# ProPrj___2024-10-15.net
KiCad netlist of a schematic drawn in EasyEDA Pro
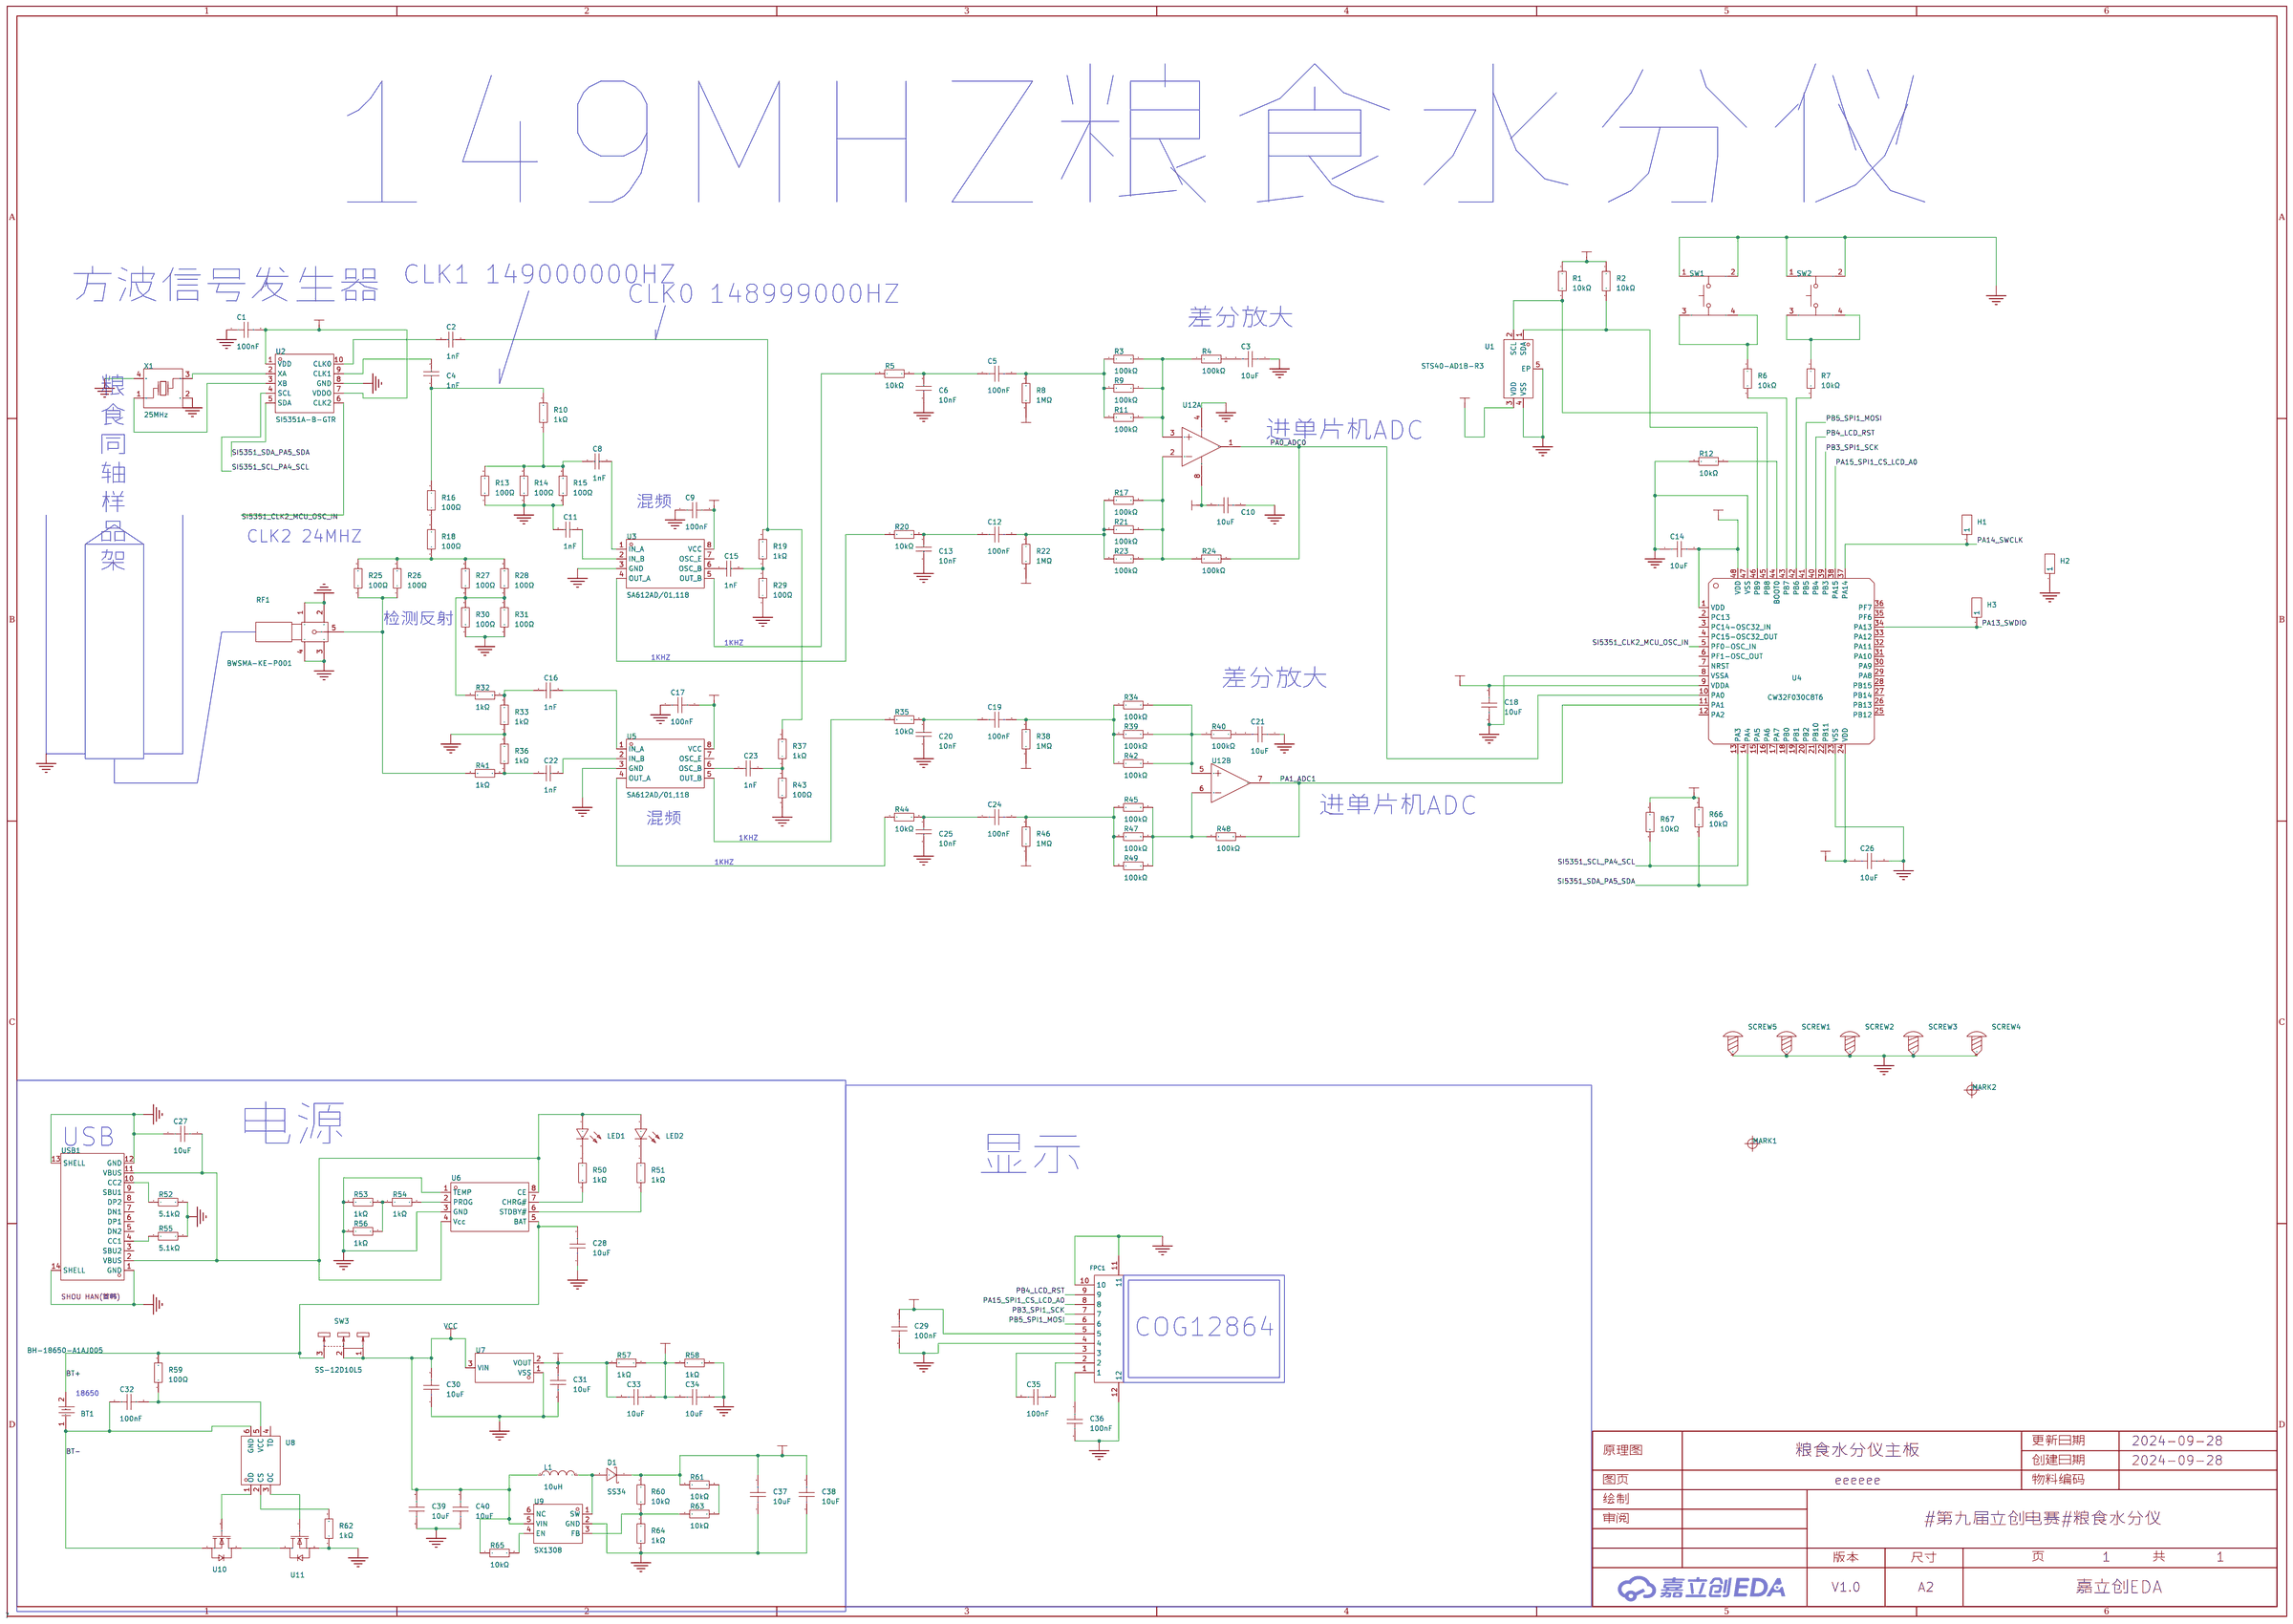
[diagram p0: schematic sheet]

(export (version "E")
  (design (tool "Eeschema 10.0.6"))
  (components
    (comp (ref "BT1")
      (value "BH-18650-A1AJ005")
      (footprint "easyedapro:BAT-TH_BH-18650-A1AJ005")
      (description "连接器类型:电池盒;适用电池规格:CR18650;触点电镀:镍;工作温度范围:-10°C~+100°C;")
      (fields (field (name "Manufacturer") "MYOUNG(美阳)"))
      (libsource (lib "easyedapro") (part "BH-18650-A1AJ005"))
    )
    (comp (ref "C1")
      (value "100nF")
      (footprint "easyedapro:C0603")
      (description "容值:100nF;精度:±10%;额定电压:50V;材质(温度系数):X7R;")
      (fields
        (field (name "Manufacturer Part") "CC0603KRX7R9BB104")
        (field (name "Manufacturer") "YAGEO(国巨)")
      )
      (libsource (lib "easyedapro") (part "CC0603KRX7R9BB104"))
    )
    (comp (ref "C2")
      (value "1nF")
      (footprint "easyedapro:C0603")
      (description "容值:1nF;精度:±5%;额定电压:50V;材质(温度系数):NP0;")
      (fields
        (field (name "Manufacturer Part") "CC0603JRNPO9BN102")
        (field (name "Manufacturer") "YAGEO(国巨)")
      )
      (libsource (lib "easyedapro") (part "CC0603JRNPO9BN102"))
    )
    (comp (ref "C3")
      (value "10uF")
      (footprint "easyedapro:C0603")
      (description "容值:10uF;精度:±10%;额定电压:10V;材质(温度系数):X5R;")
      (fields
        (field (name "Manufacturer Part") "CL10A106KP8NNNC")
        (field (name "Manufacturer") "SAMSUNG(三星)")
      )
      (libsource (lib "easyedapro") (part "CL10A106KP8NNNC"))
    )
    (comp (ref "C4")
      (value "1nF")
      (footprint "easyedapro:C0603")
      (description "容值:1nF;精度:±5%;额定电压:50V;材质(温度系数):NP0;")
      (fields
        (field (name "Manufacturer Part") "CC0603JRNPO9BN102")
        (field (name "Manufacturer") "YAGEO(国巨)")
      )
      (libsource (lib "easyedapro") (part "CC0603JRNPO9BN102"))
    )
    (comp (ref "C5")
      (value "100nF")
      (footprint "easyedapro:C0603")
      (description "容值:100nF;精度:±10%;额定电压:50V;材质(温度系数):X7R;")
      (fields
        (field (name "Manufacturer Part") "CC0603KRX7R9BB104")
        (field (name "Manufacturer") "YAGEO(国巨)")
      )
      (libsource (lib "easyedapro") (part "CC0603KRX7R9BB104"))
    )
    (comp (ref "C6")
      (value "10nF")
      (footprint "easyedapro:C0603")
      (description "容值:10nF;精度:±10%;额定电压:50V;材质(温度系数):X7R;")
      (fields
        (field (name "Manufacturer Part") "CC0603KRX7R9BB103")
        (field (name "Manufacturer") "YAGEO(国巨)")
      )
      (libsource (lib "easyedapro") (part "CC0603KRX7R9BB103"))
    )
    (comp (ref "C8")
      (value "1nF")
      (footprint "easyedapro:C0603")
      (description "容值:1nF;精度:±5%;额定电压:50V;材质(温度系数):NP0;")
      (fields
        (field (name "Manufacturer Part") "CC0603JRNPO9BN102")
        (field (name "Manufacturer") "YAGEO(国巨)")
      )
      (libsource (lib "easyedapro") (part "CC0603JRNPO9BN102"))
    )
    (comp (ref "C9")
      (value "100nF")
      (footprint "easyedapro:C0603")
      (description "容值:100nF;精度:±10%;额定电压:50V;材质(温度系数):X7R;")
      (fields
        (field (name "Manufacturer Part") "CC0603KRX7R9BB104")
        (field (name "Manufacturer") "YAGEO(国巨)")
      )
      (libsource (lib "easyedapro") (part "CC0603KRX7R9BB104"))
    )
    (comp (ref "C10")
      (value "10uF")
      (footprint "easyedapro:C0603")
      (description "容值:10uF;精度:±10%;额定电压:10V;材质(温度系数):X5R;")
      (fields
        (field (name "Manufacturer Part") "CL10A106KP8NNNC")
        (field (name "Manufacturer") "SAMSUNG(三星)")
      )
      (libsource (lib "easyedapro") (part "CL10A106KP8NNNC"))
    )
    (comp (ref "C11")
      (value "1nF")
      (footprint "easyedapro:C0603")
      (description "容值:1nF;精度:±5%;额定电压:50V;材质(温度系数):NP0;")
      (fields
        (field (name "Manufacturer Part") "CC0603JRNPO9BN102")
        (field (name "Manufacturer") "YAGEO(国巨)")
      )
      (libsource (lib "easyedapro") (part "CC0603JRNPO9BN102"))
    )
    (comp (ref "C12")
      (value "100nF")
      (footprint "easyedapro:C0603")
      (description "容值:100nF;精度:±10%;额定电压:50V;材质(温度系数):X7R;")
      (fields
        (field (name "Manufacturer Part") "CC0603KRX7R9BB104")
        (field (name "Manufacturer") "YAGEO(国巨)")
      )
      (libsource (lib "easyedapro") (part "CC0603KRX7R9BB104"))
    )
    (comp (ref "C13")
      (value "10nF")
      (footprint "easyedapro:C0603")
      (description "容值:10nF;精度:±10%;额定电压:50V;材质(温度系数):X7R;")
      (fields
        (field (name "Manufacturer Part") "CC0603KRX7R9BB103")
        (field (name "Manufacturer") "YAGEO(国巨)")
      )
      (libsource (lib "easyedapro") (part "CC0603KRX7R9BB103"))
    )
    (comp (ref "C14")
      (value "10uF")
      (footprint "easyedapro:C0603")
      (description "容值:10uF;精度:±10%;额定电压:10V;材质(温度系数):X5R;")
      (fields
        (field (name "Manufacturer Part") "CL10A106KP8NNNC")
        (field (name "Manufacturer") "SAMSUNG(三星)")
      )
      (libsource (lib "easyedapro") (part "CL10A106KP8NNNC"))
    )
    (comp (ref "C15")
      (value "1nF")
      (footprint "easyedapro:C0603")
      (description "容值:1nF;精度:±5%;额定电压:50V;材质(温度系数):NP0;")
      (fields
        (field (name "Manufacturer Part") "CC0603JRNPO9BN102")
        (field (name "Manufacturer") "YAGEO(国巨)")
      )
      (libsource (lib "easyedapro") (part "CC0603JRNPO9BN102"))
    )
    (comp (ref "C16")
      (value "1nF")
      (footprint "easyedapro:C0603")
      (description "容值:1nF;精度:±5%;额定电压:50V;材质(温度系数):NP0;")
      (fields
        (field (name "Manufacturer Part") "CC0603JRNPO9BN102")
        (field (name "Manufacturer") "YAGEO(国巨)")
      )
      (libsource (lib "easyedapro") (part "CC0603JRNPO9BN102"))
    )
    (comp (ref "C17")
      (value "100nF")
      (footprint "easyedapro:C0603")
      (description "容值:100nF;精度:±10%;额定电压:50V;材质(温度系数):X7R;")
      (fields
        (field (name "Manufacturer Part") "CC0603KRX7R9BB104")
        (field (name "Manufacturer") "YAGEO(国巨)")
      )
      (libsource (lib "easyedapro") (part "CC0603KRX7R9BB104"))
    )
    (comp (ref "C18")
      (value "10uF")
      (footprint "easyedapro:C0603")
      (description "容值:10uF;精度:±10%;额定电压:10V;材质(温度系数):X5R;")
      (fields
        (field (name "Manufacturer Part") "CL10A106KP8NNNC")
        (field (name "Manufacturer") "SAMSUNG(三星)")
      )
      (libsource (lib "easyedapro") (part "CL10A106KP8NNNC"))
    )
    (comp (ref "C19")
      (value "100nF")
      (footprint "easyedapro:C0603")
      (description "容值:100nF;精度:±10%;额定电压:50V;材质(温度系数):X7R;")
      (fields
        (field (name "Manufacturer Part") "CC0603KRX7R9BB104")
        (field (name "Manufacturer") "YAGEO(国巨)")
      )
      (libsource (lib "easyedapro") (part "CC0603KRX7R9BB104"))
    )
    (comp (ref "C20")
      (value "10nF")
      (footprint "easyedapro:C0603")
      (description "容值:10nF;精度:±10%;额定电压:50V;材质(温度系数):X7R;")
      (fields
        (field (name "Manufacturer Part") "CC0603KRX7R9BB103")
        (field (name "Manufacturer") "YAGEO(国巨)")
      )
      (libsource (lib "easyedapro") (part "CC0603KRX7R9BB103"))
    )
    (comp (ref "C21")
      (value "10uF")
      (footprint "easyedapro:C0603")
      (description "容值:10uF;精度:±10%;额定电压:10V;材质(温度系数):X5R;")
      (fields
        (field (name "Manufacturer Part") "CL10A106KP8NNNC")
        (field (name "Manufacturer") "SAMSUNG(三星)")
      )
      (libsource (lib "easyedapro") (part "CL10A106KP8NNNC"))
    )
    (comp (ref "C22")
      (value "1nF")
      (footprint "easyedapro:C0603")
      (description "容值:1nF;精度:±5%;额定电压:50V;材质(温度系数):NP0;")
      (fields
        (field (name "Manufacturer Part") "CC0603JRNPO9BN102")
        (field (name "Manufacturer") "YAGEO(国巨)")
      )
      (libsource (lib "easyedapro") (part "CC0603JRNPO9BN102"))
    )
    (comp (ref "C23")
      (value "1nF")
      (footprint "easyedapro:C0603")
      (description "容值:1nF;精度:±5%;额定电压:50V;材质(温度系数):NP0;")
      (fields
        (field (name "Manufacturer Part") "CC0603JRNPO9BN102")
        (field (name "Manufacturer") "YAGEO(国巨)")
      )
      (libsource (lib "easyedapro") (part "CC0603JRNPO9BN102"))
    )
    (comp (ref "C24")
      (value "100nF")
      (footprint "easyedapro:C0603")
      (description "容值:100nF;精度:±10%;额定电压:50V;材质(温度系数):X7R;")
      (fields
        (field (name "Manufacturer Part") "CC0603KRX7R9BB104")
        (field (name "Manufacturer") "YAGEO(国巨)")
      )
      (libsource (lib "easyedapro") (part "CC0603KRX7R9BB104"))
    )
    (comp (ref "C25")
      (value "10nF")
      (footprint "easyedapro:C0603")
      (description "容值:10nF;精度:±10%;额定电压:50V;材质(温度系数):X7R;")
      (fields
        (field (name "Manufacturer Part") "CC0603KRX7R9BB103")
        (field (name "Manufacturer") "YAGEO(国巨)")
      )
      (libsource (lib "easyedapro") (part "CC0603KRX7R9BB103"))
    )
    (comp (ref "C26")
      (value "10uF")
      (footprint "easyedapro:C0603")
      (description "容值:10uF;精度:±10%;额定电压:10V;材质(温度系数):X5R;")
      (fields
        (field (name "Manufacturer Part") "CL10A106KP8NNNC")
        (field (name "Manufacturer") "SAMSUNG(三星)")
      )
      (libsource (lib "easyedapro") (part "CL10A106KP8NNNC"))
    )
    (comp (ref "C27")
      (value "10uF")
      (footprint "easyedapro:C0603")
      (description "容值:10uF;精度:±10%;额定电压:10V;材质(温度系数):X5R;")
      (fields
        (field (name "Manufacturer Part") "CL10A106KP8NNNC")
        (field (name "Manufacturer") "SAMSUNG(三星)")
      )
      (libsource (lib "easyedapro") (part "CL10A106KP8NNNC"))
    )
    (comp (ref "C28")
      (value "10uF")
      (footprint "easyedapro:C0603")
      (description "容值:10uF;精度:±10%;额定电压:10V;材质(温度系数):X5R;")
      (fields
        (field (name "Manufacturer Part") "CL10A106KP8NNNC")
        (field (name "Manufacturer") "SAMSUNG(三星)")
      )
      (libsource (lib "easyedapro") (part "CL10A106KP8NNNC"))
    )
    (comp (ref "C29")
      (value "100nF")
      (footprint "easyedapro:C0603")
      (description "容值:100nF;精度:±10%;额定电压:50V;材质(温度系数):X7R;")
      (fields
        (field (name "Manufacturer Part") "CC0603KRX7R9BB104")
        (field (name "Manufacturer") "YAGEO(国巨)")
      )
      (libsource (lib "easyedapro") (part "CC0603KRX7R9BB104"))
    )
    (comp (ref "C30")
      (value "10uF")
      (footprint "easyedapro:C0603")
      (description "容值:10uF;精度:±10%;额定电压:10V;材质(温度系数):X5R;")
      (fields
        (field (name "Manufacturer Part") "CL10A106KP8NNNC")
        (field (name "Manufacturer") "SAMSUNG(三星)")
      )
      (libsource (lib "easyedapro") (part "CL10A106KP8NNNC"))
    )
    (comp (ref "C31")
      (value "10uF")
      (footprint "easyedapro:C0603")
      (description "容值:10uF;精度:±10%;额定电压:10V;材质(温度系数):X5R;")
      (fields
        (field (name "Manufacturer Part") "CL10A106KP8NNNC")
        (field (name "Manufacturer") "SAMSUNG(三星)")
      )
      (libsource (lib "easyedapro") (part "CL10A106KP8NNNC"))
    )
    (comp (ref "C32")
      (value "100nF")
      (footprint "easyedapro:C0603")
      (description "容值:100nF;精度:±10%;额定电压:50V;材质(温度系数):X7R;")
      (fields
        (field (name "Manufacturer Part") "CC0603KRX7R9BB104")
        (field (name "Manufacturer") "YAGEO(国巨)")
      )
      (libsource (lib "easyedapro") (part "CC0603KRX7R9BB104"))
    )
    (comp (ref "C33")
      (value "10uF")
      (footprint "easyedapro:C0603")
      (description "容值:10uF;精度:±10%;额定电压:10V;材质(温度系数):X5R;")
      (fields
        (field (name "Manufacturer Part") "CL10A106KP8NNNC")
        (field (name "Manufacturer") "SAMSUNG(三星)")
      )
      (libsource (lib "easyedapro") (part "CL10A106KP8NNNC"))
    )
    (comp (ref "C34")
      (value "10uF")
      (footprint "easyedapro:C0603")
      (description "容值:10uF;精度:±10%;额定电压:10V;材质(温度系数):X5R;")
      (fields
        (field (name "Manufacturer Part") "CL10A106KP8NNNC")
        (field (name "Manufacturer") "SAMSUNG(三星)")
      )
      (libsource (lib "easyedapro") (part "CL10A106KP8NNNC"))
    )
    (comp (ref "C35")
      (value "100nF")
      (footprint "easyedapro:C0603")
      (description "容值:100nF;精度:±10%;额定电压:50V;材质(温度系数):X7R;")
      (fields
        (field (name "Manufacturer Part") "CC0603KRX7R9BB104")
        (field (name "Manufacturer") "YAGEO(国巨)")
      )
      (libsource (lib "easyedapro") (part "CC0603KRX7R9BB104"))
    )
    (comp (ref "C36")
      (value "100nF")
      (footprint "easyedapro:C0603")
      (description "容值:100nF;精度:±10%;额定电压:50V;材质(温度系数):X7R;")
      (fields
        (field (name "Manufacturer Part") "CC0603KRX7R9BB104")
        (field (name "Manufacturer") "YAGEO(国巨)")
      )
      (libsource (lib "easyedapro") (part "CC0603KRX7R9BB104"))
    )
    (comp (ref "C37")
      (value "10uF")
      (footprint "easyedapro:C0603")
      (description "容值:10uF;精度:±10%;额定电压:10V;材质(温度系数):X5R;")
      (fields
        (field (name "Manufacturer Part") "CL10A106KP8NNNC")
        (field (name "Manufacturer") "SAMSUNG(三星)")
      )
      (libsource (lib "easyedapro") (part "CL10A106KP8NNNC"))
    )
    (comp (ref "C38")
      (value "10uF")
      (footprint "easyedapro:C0603")
      (description "容值:10uF;精度:±10%;额定电压:10V;材质(温度系数):X5R;")
      (fields
        (field (name "Manufacturer Part") "CL10A106KP8NNNC")
        (field (name "Manufacturer") "SAMSUNG(三星)")
      )
      (libsource (lib "easyedapro") (part "CL10A106KP8NNNC"))
    )
    (comp (ref "C39")
      (value "10uF")
      (footprint "easyedapro:C0603")
      (description "容值:10uF;精度:±10%;额定电压:10V;材质(温度系数):X5R;")
      (fields
        (field (name "Manufacturer Part") "CL10A106KP8NNNC")
        (field (name "Manufacturer") "SAMSUNG(三星)")
      )
      (libsource (lib "easyedapro") (part "CL10A106KP8NNNC"))
    )
    (comp (ref "C40")
      (value "10uF")
      (footprint "easyedapro:C0603")
      (description "容值:10uF;精度:±10%;额定电压:10V;材质(温度系数):X5R;")
      (fields
        (field (name "Manufacturer Part") "CL10A106KP8NNNC")
        (field (name "Manufacturer") "SAMSUNG(三星)")
      )
      (libsource (lib "easyedapro") (part "CL10A106KP8NNNC"))
    )
    (comp (ref "D1")
      (value "SS34")
      (footprint "easyedapro:SMA_L4.3-W2.6-LS5.2-RD")
      (description "二极管配置:独立式;正向压降(Vf):550mV@3A;直流反向耐压(Vr):40V;整流电流:3A;")
      (fields (field (name "Manufacturer") "MDD(辰达半导体)"))
      (libsource (lib "easyedapro") (part "SS34_C8678"))
    )
    (comp (ref "FPC1")
      (value "{ManufacturerPart!}")
      (footprint "easyedapro:FPC-SMD_10P-P1.0_FGS-XJ-H2.0")
      (description "间距:1mm;触点数量:10;锁定特性:翻盖式;安装类型:卧贴;触点类型:下接;")
      (fields (field (name "Manufacturer Part") "AFA01-S10FCA-00") (field (name "Manufacturer") "JS(钜硕电子)"))
      (libsource (lib "easyedapro") (part "AFA01-S10FCA-00"))
    )
    (comp (ref "H1")
      (value "~")
      (footprint "easyedapro:HDR-TH_1P-V-M_XKB_X4611WV-01I-C28D40")
      (libsource (lib "easyedapro") (part "HDR_1x1"))
    )
    (comp (ref "H2")
      (value "~")
      (footprint "easyedapro:HDR-TH_1P-V-M_XKB_X4611WV-01I-C28D40")
      (libsource (lib "easyedapro") (part "HDR_1x1"))
    )
    (comp (ref "H3")
      (value "~")
      (footprint "easyedapro:HDR-TH_1P-V-M_XKB_X4611WV-01I-C28D40")
      (libsource (lib "easyedapro") (part "HDR_1x1"))
    )
    (comp (ref "L1")
      (value "10uH")
      (footprint "easyedapro:IND-SMD_L6.0-W6.0_SWPA6045S")
      (description "电感值:10uH;精度:±20%;额定电流:2.45A;饱和电流(Isat):3.5A;类型:-;")
      (fields (field (name "Manufacturer Part") "SWPA6045S100MT") (field (name "Manufacturer") "Sunlord(顺络)"))
      (libsource (lib "easyedapro") (part "SWPA6045S100MT"))
    )
    (comp (ref "LED1")
      (value "204-10SURD/S530-A3-L")
      (footprint "easyedapro:LED-TH_BD3.0-P2.54-FD")
      (description "发光颜色:红灯;二极管配置:-;主波长:624nm;色温:-;功率:60mW;安装方式:-;")
      (fields (field (name "Manufacturer") "EVERLIGHT(亿光)"))
      (libsource (lib "easyedapro") (part "204-10SURD/S530-A3-L"))
    )
    (comp (ref "LED2")
      (value "204-10SURD/S530-A3-L")
      (footprint "easyedapro:LED-TH_BD3.0-P2.54-FD")
      (description "发光颜色:红灯;二极管配置:-;主波长:624nm;色温:-;功率:60mW;安装方式:-;")
      (fields (field (name "Manufacturer") "EVERLIGHT(亿光)"))
      (libsource (lib "easyedapro") (part "204-10SURD/S530-A3-L"))
    )
    (comp (ref "MARK1")
      (value "~")
      (footprint "easyedapro:Mark-Point-1mm")
      (description "Mark点")
      (libsource (lib "easyedapro") (part "Mark-Point"))
    )
    (comp (ref "MARK2")
      (value "~")
      (footprint "easyedapro:Mark-Point-1mm")
      (description "Mark点")
      (libsource (lib "easyedapro") (part "Mark-Point"))
    )
    (comp (ref "R1")
      (value "10kΩ")
      (footprint "easyedapro:R0603")
      (description "电阻类型:厚膜电阻;阻值:10kΩ;精度:±1%;功率:100mW;")
      (fields (field (name "Manufacturer Part") "RC0603FR-0710KL") (field (name "Manufacturer") "YAGEO(国巨)"))
      (libsource (lib "easyedapro") (part "RC0603FR-0710KL"))
    )
    (comp (ref "R2")
      (value "10kΩ")
      (footprint "easyedapro:R0603")
      (description "电阻类型:厚膜电阻;阻值:10kΩ;精度:±1%;功率:100mW;")
      (fields (field (name "Manufacturer Part") "RC0603FR-0710KL") (field (name "Manufacturer") "YAGEO(国巨)"))
      (libsource (lib "easyedapro") (part "RC0603FR-0710KL"))
    )
    (comp (ref "R3")
      (value "100kΩ")
      (footprint "easyedapro:R0603")
      (description "电阻类型:厚膜电阻;阻值:100kΩ;精度:±1%;功率:100mW;")
      (fields (field (name "Manufacturer Part") "RC0603FR-07100KL") (field (name "Manufacturer") "YAGEO(国巨)"))
      (libsource (lib "easyedapro") (part "RC0603FR-07100KL"))
    )
    (comp (ref "R4")
      (value "100kΩ")
      (footprint "easyedapro:R0603")
      (description "电阻类型:厚膜电阻;阻值:100kΩ;精度:±1%;功率:100mW;")
      (fields (field (name "Manufacturer Part") "RC0603FR-07100KL") (field (name "Manufacturer") "YAGEO(国巨)"))
      (libsource (lib "easyedapro") (part "RC0603FR-07100KL"))
    )
    (comp (ref "R5")
      (value "10kΩ")
      (footprint "easyedapro:R0603")
      (description "电阻类型:厚膜电阻;阻值:10kΩ;精度:±1%;功率:100mW;")
      (fields (field (name "Manufacturer Part") "RC0603FR-0710KL") (field (name "Manufacturer") "YAGEO(国巨)"))
      (libsource (lib "easyedapro") (part "RC0603FR-0710KL"))
    )
    (comp (ref "R6")
      (value "10kΩ")
      (footprint "easyedapro:R0603")
      (description "电阻类型:厚膜电阻;阻值:10kΩ;精度:±1%;功率:100mW;")
      (fields (field (name "Manufacturer Part") "RC0603FR-0710KL") (field (name "Manufacturer") "YAGEO(国巨)"))
      (libsource (lib "easyedapro") (part "RC0603FR-0710KL"))
    )
    (comp (ref "R7")
      (value "10kΩ")
      (footprint "easyedapro:R0603")
      (description "电阻类型:厚膜电阻;阻值:10kΩ;精度:±1%;功率:100mW;")
      (fields (field (name "Manufacturer Part") "RC0603FR-0710KL") (field (name "Manufacturer") "YAGEO(国巨)"))
      (libsource (lib "easyedapro") (part "RC0603FR-0710KL"))
    )
    (comp (ref "R8")
      (value "1MΩ")
      (footprint "easyedapro:R0603")
      (description "电阻类型:厚膜电阻;阻值:1MΩ;精度:±1%;功率:100mW;")
      (fields
        (field (name "Manufacturer Part") "0603WAF1004T5E")
        (field (name "Manufacturer") "UNI-ROYAL(厚声)")
      )
      (libsource (lib "easyedapro") (part "0603WAF1004T5E"))
    )
    (comp (ref "R9")
      (value "100kΩ")
      (footprint "easyedapro:R0603")
      (description "电阻类型:厚膜电阻;阻值:100kΩ;精度:±1%;功率:100mW;")
      (fields (field (name "Manufacturer Part") "RC0603FR-07100KL") (field (name "Manufacturer") "YAGEO(国巨)"))
      (libsource (lib "easyedapro") (part "RC0603FR-07100KL"))
    )
    (comp (ref "R10")
      (value "1kΩ")
      (footprint "easyedapro:R0603")
      (description "电阻类型:厚膜电阻;阻值:1kΩ;精度:±1%;功率:100mW;")
      (fields (field (name "Manufacturer Part") "RC0603FR-071KL") (field (name "Manufacturer") "YAGEO(国巨)"))
      (libsource (lib "easyedapro") (part "RC0603FR-071KL"))
    )
    (comp (ref "R11")
      (value "100kΩ")
      (footprint "easyedapro:R0603")
      (description "电阻类型:厚膜电阻;阻值:100kΩ;精度:±1%;功率:100mW;")
      (fields (field (name "Manufacturer Part") "RC0603FR-07100KL") (field (name "Manufacturer") "YAGEO(国巨)"))
      (libsource (lib "easyedapro") (part "RC0603FR-07100KL"))
    )
    (comp (ref "R12")
      (value "10kΩ")
      (footprint "easyedapro:R0603")
      (description "电阻类型:厚膜电阻;阻值:10kΩ;精度:±1%;功率:100mW;")
      (fields (field (name "Manufacturer Part") "RC0603FR-0710KL") (field (name "Manufacturer") "YAGEO(国巨)"))
      (libsource (lib "easyedapro") (part "RC0603FR-0710KL"))
    )
    (comp (ref "R13")
      (value "100Ω")
      (footprint "easyedapro:R0603")
      (description "电阻类型:厚膜电阻;阻值:100Ω;精度:±1%;功率:100mW;")
      (fields (field (name "Manufacturer Part") "RC0603FR-07100RL") (field (name "Manufacturer") "YAGEO(国巨)"))
      (libsource (lib "easyedapro") (part "RC0603FR-07100RL"))
    )
    (comp (ref "R14")
      (value "100Ω")
      (footprint "easyedapro:R0603")
      (description "电阻类型:厚膜电阻;阻值:100Ω;精度:±1%;功率:100mW;")
      (fields (field (name "Manufacturer Part") "RC0603FR-07100RL") (field (name "Manufacturer") "YAGEO(国巨)"))
      (libsource (lib "easyedapro") (part "RC0603FR-07100RL"))
    )
    (comp (ref "R15")
      (value "100Ω")
      (footprint "easyedapro:R0603")
      (description "电阻类型:厚膜电阻;阻值:100Ω;精度:±1%;功率:100mW;")
      (fields (field (name "Manufacturer Part") "RC0603FR-07100RL") (field (name "Manufacturer") "YAGEO(国巨)"))
      (libsource (lib "easyedapro") (part "RC0603FR-07100RL"))
    )
    (comp (ref "R16")
      (value "100Ω")
      (footprint "easyedapro:R0603")
      (description "电阻类型:厚膜电阻;阻值:100Ω;精度:±1%;功率:100mW;")
      (fields (field (name "Manufacturer Part") "RC0603FR-07100RL") (field (name "Manufacturer") "YAGEO(国巨)"))
      (libsource (lib "easyedapro") (part "RC0603FR-07100RL"))
    )
    (comp (ref "R17")
      (value "100kΩ")
      (footprint "easyedapro:R0603")
      (description "电阻类型:厚膜电阻;阻值:100kΩ;精度:±1%;功率:100mW;")
      (fields (field (name "Manufacturer Part") "RC0603FR-07100KL") (field (name "Manufacturer") "YAGEO(国巨)"))
      (libsource (lib "easyedapro") (part "RC0603FR-07100KL"))
    )
    (comp (ref "R18")
      (value "100Ω")
      (footprint "easyedapro:R0603")
      (description "电阻类型:厚膜电阻;阻值:100Ω;精度:±1%;功率:100mW;")
      (fields (field (name "Manufacturer Part") "RC0603FR-07100RL") (field (name "Manufacturer") "YAGEO(国巨)"))
      (libsource (lib "easyedapro") (part "RC0603FR-07100RL"))
    )
    (comp (ref "R19")
      (value "1kΩ")
      (footprint "easyedapro:R0603")
      (description "电阻类型:厚膜电阻;阻值:1kΩ;精度:±1%;功率:100mW;")
      (fields (field (name "Manufacturer Part") "RC0603FR-071KL") (field (name "Manufacturer") "YAGEO(国巨)"))
      (libsource (lib "easyedapro") (part "RC0603FR-071KL"))
    )
    (comp (ref "R20")
      (value "10kΩ")
      (footprint "easyedapro:R0603")
      (description "电阻类型:厚膜电阻;阻值:10kΩ;精度:±1%;功率:100mW;")
      (fields (field (name "Manufacturer Part") "RC0603FR-0710KL") (field (name "Manufacturer") "YAGEO(国巨)"))
      (libsource (lib "easyedapro") (part "RC0603FR-0710KL"))
    )
    (comp (ref "R21")
      (value "100kΩ")
      (footprint "easyedapro:R0603")
      (description "电阻类型:厚膜电阻;阻值:100kΩ;精度:±1%;功率:100mW;")
      (fields (field (name "Manufacturer Part") "RC0603FR-07100KL") (field (name "Manufacturer") "YAGEO(国巨)"))
      (libsource (lib "easyedapro") (part "RC0603FR-07100KL"))
    )
    (comp (ref "R22")
      (value "1MΩ")
      (footprint "easyedapro:R0603")
      (description "电阻类型:厚膜电阻;阻值:1MΩ;精度:±1%;功率:100mW;")
      (fields
        (field (name "Manufacturer Part") "0603WAF1004T5E")
        (field (name "Manufacturer") "UNI-ROYAL(厚声)")
      )
      (libsource (lib "easyedapro") (part "0603WAF1004T5E"))
    )
    (comp (ref "R23")
      (value "100kΩ")
      (footprint "easyedapro:R0603")
      (description "电阻类型:厚膜电阻;阻值:100kΩ;精度:±1%;功率:100mW;")
      (fields (field (name "Manufacturer Part") "RC0603FR-07100KL") (field (name "Manufacturer") "YAGEO(国巨)"))
      (libsource (lib "easyedapro") (part "RC0603FR-07100KL"))
    )
    (comp (ref "R24")
      (value "100kΩ")
      (footprint "easyedapro:R0603")
      (description "电阻类型:厚膜电阻;阻值:100kΩ;精度:±1%;功率:100mW;")
      (fields (field (name "Manufacturer Part") "RC0603FR-07100KL") (field (name "Manufacturer") "YAGEO(国巨)"))
      (libsource (lib "easyedapro") (part "RC0603FR-07100KL"))
    )
    (comp (ref "R25")
      (value "100Ω")
      (footprint "easyedapro:R0603")
      (description "电阻类型:厚膜电阻;阻值:100Ω;精度:±1%;功率:100mW;")
      (fields (field (name "Manufacturer Part") "RC0603FR-07100RL") (field (name "Manufacturer") "YAGEO(国巨)"))
      (libsource (lib "easyedapro") (part "RC0603FR-07100RL"))
    )
    (comp (ref "R26")
      (value "100Ω")
      (footprint "easyedapro:R0603")
      (description "电阻类型:厚膜电阻;阻值:100Ω;精度:±1%;功率:100mW;")
      (fields (field (name "Manufacturer Part") "RC0603FR-07100RL") (field (name "Manufacturer") "YAGEO(国巨)"))
      (libsource (lib "easyedapro") (part "RC0603FR-07100RL"))
    )
    (comp (ref "R27")
      (value "100Ω")
      (footprint "easyedapro:R0603")
      (description "电阻类型:厚膜电阻;阻值:100Ω;精度:±1%;功率:100mW;")
      (fields (field (name "Manufacturer Part") "RC0603FR-07100RL") (field (name "Manufacturer") "YAGEO(国巨)"))
      (libsource (lib "easyedapro") (part "RC0603FR-07100RL"))
    )
    (comp (ref "R28")
      (value "100Ω")
      (footprint "easyedapro:R0603")
      (description "电阻类型:厚膜电阻;阻值:100Ω;精度:±1%;功率:100mW;")
      (fields (field (name "Manufacturer Part") "RC0603FR-07100RL") (field (name "Manufacturer") "YAGEO(国巨)"))
      (libsource (lib "easyedapro") (part "RC0603FR-07100RL"))
    )
    (comp (ref "R29")
      (value "100Ω")
      (footprint "easyedapro:R0603")
      (description "电阻类型:厚膜电阻;阻值:100Ω;精度:±1%;功率:100mW;")
      (fields (field (name "Manufacturer Part") "RC0603FR-07100RL") (field (name "Manufacturer") "YAGEO(国巨)"))
      (libsource (lib "easyedapro") (part "RC0603FR-07100RL"))
    )
    (comp (ref "R30")
      (value "100Ω")
      (footprint "easyedapro:R0603")
      (description "电阻类型:厚膜电阻;阻值:100Ω;精度:±1%;功率:100mW;")
      (fields (field (name "Manufacturer Part") "RC0603FR-07100RL") (field (name "Manufacturer") "YAGEO(国巨)"))
      (libsource (lib "easyedapro") (part "RC0603FR-07100RL"))
    )
    (comp (ref "R31")
      (value "100Ω")
      (footprint "easyedapro:R0603")
      (description "电阻类型:厚膜电阻;阻值:100Ω;精度:±1%;功率:100mW;")
      (fields (field (name "Manufacturer Part") "RC0603FR-07100RL") (field (name "Manufacturer") "YAGEO(国巨)"))
      (libsource (lib "easyedapro") (part "RC0603FR-07100RL"))
    )
    (comp (ref "R32")
      (value "1kΩ")
      (footprint "easyedapro:R0603")
      (description "电阻类型:厚膜电阻;阻值:1kΩ;精度:±1%;功率:100mW;")
      (fields (field (name "Manufacturer Part") "RC0603FR-071KL") (field (name "Manufacturer") "YAGEO(国巨)"))
      (libsource (lib "easyedapro") (part "RC0603FR-071KL"))
    )
    (comp (ref "R33")
      (value "1kΩ")
      (footprint "easyedapro:R0603")
      (description "电阻类型:厚膜电阻;阻值:1kΩ;精度:±1%;功率:100mW;")
      (fields (field (name "Manufacturer Part") "RC0603FR-071KL") (field (name "Manufacturer") "YAGEO(国巨)"))
      (libsource (lib "easyedapro") (part "RC0603FR-071KL"))
    )
    (comp (ref "R34")
      (value "100kΩ")
      (footprint "easyedapro:R0603")
      (description "电阻类型:厚膜电阻;阻值:100kΩ;精度:±1%;功率:100mW;")
      (fields (field (name "Manufacturer Part") "RC0603FR-07100KL") (field (name "Manufacturer") "YAGEO(国巨)"))
      (libsource (lib "easyedapro") (part "RC0603FR-07100KL"))
    )
    (comp (ref "R35")
      (value "10kΩ")
      (footprint "easyedapro:R0603")
      (description "电阻类型:厚膜电阻;阻值:10kΩ;精度:±1%;功率:100mW;")
      (fields (field (name "Manufacturer Part") "RC0603FR-0710KL") (field (name "Manufacturer") "YAGEO(国巨)"))
      (libsource (lib "easyedapro") (part "RC0603FR-0710KL"))
    )
    (comp (ref "R36")
      (value "1kΩ")
      (footprint "easyedapro:R0603")
      (description "电阻类型:厚膜电阻;阻值:1kΩ;精度:±1%;功率:100mW;")
      (fields (field (name "Manufacturer Part") "RC0603FR-071KL") (field (name "Manufacturer") "YAGEO(国巨)"))
      (libsource (lib "easyedapro") (part "RC0603FR-071KL"))
    )
    (comp (ref "R37")
      (value "1kΩ")
      (footprint "easyedapro:R0603")
      (description "电阻类型:厚膜电阻;阻值:1kΩ;精度:±1%;功率:100mW;")
      (fields (field (name "Manufacturer Part") "RC0603FR-071KL") (field (name "Manufacturer") "YAGEO(国巨)"))
      (libsource (lib "easyedapro") (part "RC0603FR-071KL"))
    )
    (comp (ref "R38")
      (value "1MΩ")
      (footprint "easyedapro:R0603")
      (description "电阻类型:厚膜电阻;阻值:1MΩ;精度:±1%;功率:100mW;")
      (fields
        (field (name "Manufacturer Part") "0603WAF1004T5E")
        (field (name "Manufacturer") "UNI-ROYAL(厚声)")
      )
      (libsource (lib "easyedapro") (part "0603WAF1004T5E"))
    )
    (comp (ref "R39")
      (value "100kΩ")
      (footprint "easyedapro:R0603")
      (description "电阻类型:厚膜电阻;阻值:100kΩ;精度:±1%;功率:100mW;")
      (fields (field (name "Manufacturer Part") "RC0603FR-07100KL") (field (name "Manufacturer") "YAGEO(国巨)"))
      (libsource (lib "easyedapro") (part "RC0603FR-07100KL"))
    )
    (comp (ref "R40")
      (value "100kΩ")
      (footprint "easyedapro:R0603")
      (description "电阻类型:厚膜电阻;阻值:100kΩ;精度:±1%;功率:100mW;")
      (fields (field (name "Manufacturer Part") "RC0603FR-07100KL") (field (name "Manufacturer") "YAGEO(国巨)"))
      (libsource (lib "easyedapro") (part "RC0603FR-07100KL"))
    )
    (comp (ref "R41")
      (value "1kΩ")
      (footprint "easyedapro:R0603")
      (description "电阻类型:厚膜电阻;阻值:1kΩ;精度:±1%;功率:100mW;")
      (fields (field (name "Manufacturer Part") "RC0603FR-071KL") (field (name "Manufacturer") "YAGEO(国巨)"))
      (libsource (lib "easyedapro") (part "RC0603FR-071KL"))
    )
    (comp (ref "R42")
      (value "100kΩ")
      (footprint "easyedapro:R0603")
      (description "电阻类型:厚膜电阻;阻值:100kΩ;精度:±1%;功率:100mW;")
      (fields (field (name "Manufacturer Part") "RC0603FR-07100KL") (field (name "Manufacturer") "YAGEO(国巨)"))
      (libsource (lib "easyedapro") (part "RC0603FR-07100KL"))
    )
    (comp (ref "R43")
      (value "100Ω")
      (footprint "easyedapro:R0603")
      (description "电阻类型:厚膜电阻;阻值:100Ω;精度:±1%;功率:100mW;")
      (fields (field (name "Manufacturer Part") "RC0603FR-07100RL") (field (name "Manufacturer") "YAGEO(国巨)"))
      (libsource (lib "easyedapro") (part "RC0603FR-07100RL"))
    )
    (comp (ref "R44")
      (value "10kΩ")
      (footprint "easyedapro:R0603")
      (description "电阻类型:厚膜电阻;阻值:10kΩ;精度:±1%;功率:100mW;")
      (fields (field (name "Manufacturer Part") "RC0603FR-0710KL") (field (name "Manufacturer") "YAGEO(国巨)"))
      (libsource (lib "easyedapro") (part "RC0603FR-0710KL"))
    )
    (comp (ref "R45")
      (value "100kΩ")
      (footprint "easyedapro:R0603")
      (description "电阻类型:厚膜电阻;阻值:100kΩ;精度:±1%;功率:100mW;")
      (fields (field (name "Manufacturer Part") "RC0603FR-07100KL") (field (name "Manufacturer") "YAGEO(国巨)"))
      (libsource (lib "easyedapro") (part "RC0603FR-07100KL"))
    )
    (comp (ref "R46")
      (value "1MΩ")
      (footprint "easyedapro:R0603")
      (description "电阻类型:厚膜电阻;阻值:1MΩ;精度:±1%;功率:100mW;")
      (fields
        (field (name "Manufacturer Part") "0603WAF1004T5E")
        (field (name "Manufacturer") "UNI-ROYAL(厚声)")
      )
      (libsource (lib "easyedapro") (part "0603WAF1004T5E"))
    )
    (comp (ref "R47")
      (value "100kΩ")
      (footprint "easyedapro:R0603")
      (description "电阻类型:厚膜电阻;阻值:100kΩ;精度:±1%;功率:100mW;")
      (fields (field (name "Manufacturer Part") "RC0603FR-07100KL") (field (name "Manufacturer") "YAGEO(国巨)"))
      (libsource (lib "easyedapro") (part "RC0603FR-07100KL"))
    )
    (comp (ref "R48")
      (value "100kΩ")
      (footprint "easyedapro:R0603")
      (description "电阻类型:厚膜电阻;阻值:100kΩ;精度:±1%;功率:100mW;")
      (fields (field (name "Manufacturer Part") "RC0603FR-07100KL") (field (name "Manufacturer") "YAGEO(国巨)"))
      (libsource (lib "easyedapro") (part "RC0603FR-07100KL"))
    )
    (comp (ref "R49")
      (value "100kΩ")
      (footprint "easyedapro:R0603")
      (description "电阻类型:厚膜电阻;阻值:100kΩ;精度:±1%;功率:100mW;")
      (fields (field (name "Manufacturer Part") "RC0603FR-07100KL") (field (name "Manufacturer") "YAGEO(国巨)"))
      (libsource (lib "easyedapro") (part "RC0603FR-07100KL"))
    )
    (comp (ref "R50")
      (value "1kΩ")
      (footprint "easyedapro:R0603")
      (description "电阻类型:厚膜电阻;阻值:1kΩ;精度:±1%;功率:100mW;")
      (fields (field (name "Manufacturer Part") "RC0603FR-071KL") (field (name "Manufacturer") "YAGEO(国巨)"))
      (libsource (lib "easyedapro") (part "RC0603FR-071KL"))
    )
    (comp (ref "R51")
      (value "1kΩ")
      (footprint "easyedapro:R0603")
      (description "电阻类型:厚膜电阻;阻值:1kΩ;精度:±1%;功率:100mW;")
      (fields (field (name "Manufacturer Part") "RC0603FR-071KL") (field (name "Manufacturer") "YAGEO(国巨)"))
      (libsource (lib "easyedapro") (part "RC0603FR-071KL"))
    )
    (comp (ref "R52")
      (value "5.1kΩ")
      (footprint "easyedapro:R0603")
      (description "电阻类型:厚膜电阻;阻值:10kΩ;精度:±1%;功率:100mW;")
      (fields (field (name "Manufacturer Part") "RC0603FR-0710KL") (field (name "Manufacturer") "YAGEO(国巨)"))
      (libsource (lib "easyedapro") (part "RC0603FR-0710KL"))
    )
    (comp (ref "R53")
      (value "1kΩ")
      (footprint "easyedapro:R0603")
      (description "电阻类型:厚膜电阻;阻值:1kΩ;精度:±1%;功率:100mW;")
      (fields (field (name "Manufacturer Part") "RC0603FR-071KL") (field (name "Manufacturer") "YAGEO(国巨)"))
      (libsource (lib "easyedapro") (part "RC0603FR-071KL"))
    )
    (comp (ref "R54")
      (value "1kΩ")
      (footprint "easyedapro:R0603")
      (description "电阻类型:厚膜电阻;阻值:1kΩ;精度:±1%;功率:100mW;")
      (fields (field (name "Manufacturer Part") "RC0603FR-071KL") (field (name "Manufacturer") "YAGEO(国巨)"))
      (libsource (lib "easyedapro") (part "RC0603FR-071KL"))
    )
    (comp (ref "R55")
      (value "5.1kΩ")
      (footprint "easyedapro:R0603")
      (description "电阻类型:厚膜电阻;阻值:10kΩ;精度:±1%;功率:100mW;")
      (fields (field (name "Manufacturer Part") "RC0603FR-0710KL") (field (name "Manufacturer") "YAGEO(国巨)"))
      (libsource (lib "easyedapro") (part "RC0603FR-0710KL"))
    )
    (comp (ref "R56")
      (value "1kΩ")
      (footprint "easyedapro:R0603")
      (description "电阻类型:厚膜电阻;阻值:1kΩ;精度:±1%;功率:100mW;")
      (fields (field (name "Manufacturer Part") "RC0603FR-071KL") (field (name "Manufacturer") "YAGEO(国巨)"))
      (libsource (lib "easyedapro") (part "RC0603FR-071KL"))
    )
    (comp (ref "R57")
      (value "1kΩ")
      (footprint "easyedapro:R0603")
      (description "电阻类型:厚膜电阻;阻值:1kΩ;精度:±1%;功率:100mW;")
      (fields (field (name "Manufacturer Part") "RC0603FR-071KL") (field (name "Manufacturer") "YAGEO(国巨)"))
      (libsource (lib "easyedapro") (part "RC0603FR-071KL"))
    )
    (comp (ref "R58")
      (value "1kΩ")
      (footprint "easyedapro:R0603")
      (description "电阻类型:厚膜电阻;阻值:1kΩ;精度:±1%;功率:100mW;")
      (fields (field (name "Manufacturer Part") "RC0603FR-071KL") (field (name "Manufacturer") "YAGEO(国巨)"))
      (libsource (lib "easyedapro") (part "RC0603FR-071KL"))
    )
    (comp (ref "R59")
      (value "100Ω")
      (footprint "easyedapro:R0603")
      (description "电阻类型:厚膜电阻;阻值:100Ω;精度:±1%;功率:100mW;")
      (fields (field (name "Manufacturer Part") "RC0603FR-07100RL") (field (name "Manufacturer") "YAGEO(国巨)"))
      (libsource (lib "easyedapro") (part "RC0603FR-07100RL"))
    )
    (comp (ref "R60")
      (value "10kΩ")
      (footprint "easyedapro:R0603")
      (description "电阻类型:厚膜电阻;阻值:10kΩ;精度:±1%;功率:100mW;")
      (fields (field (name "Manufacturer Part") "RC0603FR-0710KL") (field (name "Manufacturer") "YAGEO(国巨)"))
      (libsource (lib "easyedapro") (part "RC0603FR-0710KL"))
    )
    (comp (ref "R61")
      (value "10kΩ")
      (footprint "easyedapro:R0603")
      (description "电阻类型:厚膜电阻;阻值:10kΩ;精度:±1%;功率:100mW;")
      (fields (field (name "Manufacturer Part") "RC0603FR-0710KL") (field (name "Manufacturer") "YAGEO(国巨)"))
      (libsource (lib "easyedapro") (part "RC0603FR-0710KL"))
    )
    (comp (ref "R62")
      (value "1kΩ")
      (footprint "easyedapro:R0603")
      (description "电阻类型:厚膜电阻;阻值:1kΩ;精度:±1%;功率:100mW;")
      (fields (field (name "Manufacturer Part") "RC0603FR-071KL") (field (name "Manufacturer") "YAGEO(国巨)"))
      (libsource (lib "easyedapro") (part "RC0603FR-071KL"))
    )
    (comp (ref "R63")
      (value "10kΩ")
      (footprint "easyedapro:R0603")
      (description "电阻类型:厚膜电阻;阻值:10kΩ;精度:±1%;功率:100mW;")
      (fields (field (name "Manufacturer Part") "RC0603FR-0710KL") (field (name "Manufacturer") "YAGEO(国巨)"))
      (libsource (lib "easyedapro") (part "RC0603FR-0710KL"))
    )
    (comp (ref "R64")
      (value "1kΩ")
      (footprint "easyedapro:R0603")
      (description "电阻类型:厚膜电阻;阻值:1kΩ;精度:±1%;功率:100mW;")
      (fields (field (name "Manufacturer Part") "RC0603FR-071KL") (field (name "Manufacturer") "YAGEO(国巨)"))
      (libsource (lib "easyedapro") (part "RC0603FR-071KL"))
    )
    (comp (ref "R65")
      (value "10kΩ")
      (footprint "easyedapro:R0603")
      (description "电阻类型:厚膜电阻;阻值:10kΩ;精度:±1%;功率:100mW;")
      (fields (field (name "Manufacturer Part") "RC0603FR-0710KL") (field (name "Manufacturer") "YAGEO(国巨)"))
      (libsource (lib "easyedapro") (part "RC0603FR-0710KL"))
    )
    (comp (ref "R66")
      (value "10kΩ")
      (footprint "easyedapro:R0603")
      (description "电阻类型:厚膜电阻;阻值:10kΩ;精度:±1%;功率:100mW;")
      (fields (field (name "Manufacturer Part") "RC0603FR-0710KL") (field (name "Manufacturer") "YAGEO(国巨)"))
      (libsource (lib "easyedapro") (part "RC0603FR-0710KL"))
    )
    (comp (ref "R67")
      (value "10kΩ")
      (footprint "easyedapro:R0603")
      (description "电阻类型:厚膜电阻;阻值:10kΩ;精度:±1%;功率:100mW;")
      (fields (field (name "Manufacturer Part") "RC0603FR-0710KL") (field (name "Manufacturer") "YAGEO(国巨)"))
      (libsource (lib "easyedapro") (part "RC0603FR-0710KL"))
    )
    (comp (ref "RF1")
      (value "BWSMA-KE-P001")
      (footprint "easyedapro:SMA-SMD_BWSMA-KE-P001")
      (description "连接器类型:板端;接口类型:内孔;端口数量:1;接口直径:5.2mm;接口长度/高度:-;频率-最大值:-;射频系列:SMA;阻抗:50Ω;样式:偏脚;工作温度范围:-;")
      (fields (field (name "Manufacturer") "BAT WIRELESS(蝙蝠无线)"))
      (libsource (lib "easyedapro") (part "BWSMA-KE-P001"))
    )
    (comp (ref "SCREW1")
      (value "~")
      (footprint "easyedapro:M3螺丝")
      (libsource (lib "easyedapro") (part "螺丝孔"))
    )
    (comp (ref "SCREW2")
      (value "~")
      (footprint "easyedapro:M3螺丝")
      (libsource (lib "easyedapro") (part "螺丝孔"))
    )
    (comp (ref "SCREW3")
      (value "~")
      (footprint "easyedapro:M3螺丝")
      (libsource (lib "easyedapro") (part "螺丝孔"))
    )
    (comp (ref "SCREW4")
      (value "~")
      (footprint "easyedapro:M3螺丝")
      (libsource (lib "easyedapro") (part "螺丝孔"))
    )
    (comp (ref "SCREW5")
      (value "~")
      (footprint "easyedapro:M3螺丝")
      (libsource (lib "easyedapro") (part "螺丝孔"))
    )
    (comp (ref "SW1")
      (value "{ManufacturerPart!}")
      (footprint "easyedapro:SW-TH_4P-L6.0-W6.0-P3.90-LS6.5")
      (description "触点电流:50mA;额定电压(DC):12V;额定功率:0.6W;绝缘电阻:100MΩ;电路结构:单刀单掷;安装方式:直插;带灯:无;作用力:250gf@±50gf;机械寿命:7万次;带支架:否;")
      (fields
        (field (name "Manufacturer Part") "1TS005A-2500-5001")
        (field (name "Manufacturer") "HYP(鸿源精密)")
      )
      (libsource (lib "easyedapro") (part "1TS005A-2500-5001"))
    )
    (comp (ref "SW2")
      (value "{ManufacturerPart!}")
      (footprint "easyedapro:SW-TH_4P-L6.0-W6.0-P3.90-LS6.5")
      (description "触点电流:50mA;额定电压(DC):12V;额定功率:0.6W;绝缘电阻:100MΩ;电路结构:单刀单掷;安装方式:直插;带灯:无;作用力:250gf@±50gf;机械寿命:7万次;带支架:否;")
      (fields
        (field (name "Manufacturer Part") "1TS005A-2500-5001")
        (field (name "Manufacturer") "HYP(鸿源精密)")
      )
      (libsource (lib "easyedapro") (part "1TS005A-2500-5001"))
    )
    (comp (ref "SW3")
      (value "SS-12D10L5")
      (footprint "easyedapro:SW-TH_SS-12D10L5")
      (description "电路结构:单刀双掷;安装方式:直插;开关颜色:黑色;额定电流(DC):3A;额定电压(DC):125V;额定电流(AC):3A;额定电压(AC):125V;机械寿命:1万次;")
      (fields (field (name "Manufacturer") "XKB Connectivity(中国星坤)"))
      (libsource (lib "easyedapro") (part "SS-12D10L5"))
    )
    (comp (ref "U1")
      (value "STS40-AD1B-R3")
      (footprint "easyedapro:DFN-4_L1.5-W1.5-P0.8-TL-EP")
      (description "±0.2°C 数字温度传感器")
      (fields (field (name "Manufacturer") "Sensirion(瑞士盛思锐)"))
      (libsource (lib "easyedapro") (part "STS40-AD1B-R3"))
    )
    (comp (ref "U2")
      (value "SI5351A-B-GTR")
      (footprint "easyedapro:MSOP-10_L3.0-W3.0-P0.50-LS5.0-BL")
      (description "接口类型:I2C;最大输出频率:200MHz;")
      (fields (field (name "Manufacturer") "SKYWORKS/SILICON LABS(芯科)"))
      (libsource (lib "easyedapro") (part "SI5351A-B-GTR"))
    )
    (comp (ref "U3")
      (value "SA612AD/01,118")
      (footprint "easyedapro:SO-8_L4.9-W3.9-P1.27-LS5.9-BL")
      (description "应用领域:手机,HF,VHF;频率范围:500MHz;增益:17dB;噪声系数:5dB;")
      (fields (field (name "Manufacturer") "NXP(恩智浦)"))
      (libsource (lib "easyedapro") (part "SA612AD/01,118"))
    )
    (comp (ref "U4")
      (value "CW32F030C8T6")
      (footprint "easyedapro:LQFP-48_L7.0-W7.0-P0.50-LS9.0-TL")
      (fields (field (name "Manufacturer") "CW(芯源)"))
      (libsource (lib "easyedapro") (part "CW32F030C8T6_C3019113"))
    )
    (comp (ref "U5")
      (value "SA612AD/01,118")
      (footprint "easyedapro:SO-8_L4.9-W3.9-P1.27-LS5.9-BL")
      (description "应用领域:手机,HF,VHF;频率范围:500MHz;增益:17dB;噪声系数:5dB;")
      (fields (field (name "Manufacturer") "NXP(恩智浦)"))
      (libsource (lib "easyedapro") (part "SA612AD/01,118"))
    )
    (comp (ref "U6")
      (value "WSP4056")
      (footprint "easyedapro:SOP-8_L5.1-W3.9-P1.27-LS6.0-BL")
      (fields (field (name "Manufacturer") "WINSOK(微硕)"))
      (libsource (lib "easyedapro") (part "WSP4056"))
    )
    (comp (ref "U7")
      (value "662K.")
      (footprint "easyedapro:SOT-23-3_L2.9-W1.3-P1.90-LS2.4-BR")
      (description "输出类型:-;")
      (fields (field (name "Manufacturer") "FM(富满)"))
      (libsource (lib "easyedapro") (part "662K."))
    )
    (comp (ref "U8")
      (value "WSTDW01")
      (footprint "easyedapro:SOT-23-6_L2.9-W1.6-P0.95-LS2.8-BR")
      (description "充电电池的类型:-;电池单元组数:-;最大充电电流:-;充满的电池组电压:-;最大供应电压:-;")
      (fields (field (name "Manufacturer") "WINSOK(微硕)"))
      (libsource (lib "easyedapro") (part "WSTDW01"))
    )
    (comp (ref "U9")
      (value "SX1308")
      (footprint "easyedapro:SOT-23-6_L2.9-W1.6-P0.95-LS2.8-BL")
      (description "功能类型:升压型;输入电压:2V~24V;输出电压:28V;输出电流(最大值):-;")
      (fields (field (name "Manufacturer") "SX(硕芯科技)"))
      (libsource (lib "easyedapro") (part "SX1308"))
    )
    (comp (ref "U10")
      (value "AO3400A")
      (footprint "easyedapro:SOT-23-3_L3.0-W1.6-P1.90-LS2.8-BR")
      (description "类型:N沟道;漏源电压(Vdss):30V;连续漏极电流(Id):6A;功率(Pd):1.4W;导通电阻(RDS(on)@Vgs,Id):19mΩ@10V,6.0A;")
      (fields (field (name "Manufacturer") "ElecSuper(静芯微）"))
      (libsource (lib "easyedapro") (part "AO3400A_C5224194"))
    )
    (comp (ref "U11")
      (value "AO3400A")
      (footprint "easyedapro:SOT-23-3_L3.0-W1.6-P1.90-LS2.8-BR")
      (description "类型:N沟道;漏源电压(Vdss):30V;连续漏极电流(Id):6A;功率(Pd):1.4W;导通电阻(RDS(on)@Vgs,Id):19mΩ@10V,6.0A;")
      (fields (field (name "Manufacturer") "ElecSuper(静芯微）"))
      (libsource (lib "easyedapro") (part "AO3400A_C5224194"))
    )
    (comp (ref "U12")
      (value "~")
      (footprint "easyedapro:SOP-8_L4.9-W3.9-P1.27-LS6.0-BL")
      (description "CMOS低功耗双路运算放大器")
      (fields (field (name "Manufacturer Part") "LMV358ARZ") (field (name "Manufacturer") "HTCSEMI(海天芯)"))
      (libsource (lib "easyedapro") (part "LMV358ARZ"))
    )
    (comp (ref "USB1")
      (value "TYPE-C16PIN2MD(073)")
      (footprint "easyedapro:USB-C-SMD_TYPE-C-6PIN-2MD-073")
      (description "连接器类型:Type-C;标准:-;公母:母座;触点数量:16;端口数量:1;安装方式:卧贴;额定电流 - 电源:5A;工作温度范围:-25°C~+85°C;")
      (fields (field (name "Manufacturer") "SHOU HAN(首韩)"))
      (libsource (lib "easyedapro") (part "TYPE-C 16PIN 2MD(073)"))
    )
    (comp (ref "X1")
      (value "25MHz")
      (footprint "easyedapro:CRYSTAL-SMD_4P-L3.2-W2.5-BL")
      (description "晶振类型:贴片晶振;频率:25MHz;常温频差:±10ppm;外接负载电容:10pF;频率稳定度(全温):±20ppm;")
      (fields (field (name "Manufacturer Part") "X322525MMB4SI") (field (name "Manufacturer") "YXC(扬兴晶振)"))
      (libsource (lib "easyedapro") (part "x322525mmb4si"))
    )
  )
  (nets
    (net (code "1") (name "+1.65V") (class "Default")
      (node (ref "C33") (pin "1") (pinfunction "1_1") (pintype "unspecified"))
      (node (ref "C34") (pin "2") (pinfunction "2_2") (pintype "unspecified"))
      (node (ref "R22") (pin "1") (pinfunction "1_1") (pintype "input"))
      (node (ref "R38") (pin "1") (pinfunction "1_1") (pintype "input"))
      (node (ref "R46") (pin "1") (pinfunction "1_1") (pintype "input"))
      (node (ref "R57") (pin "2") (pinfunction "2_2") (pintype "input"))
      (node (ref "R58") (pin "1") (pinfunction "1_1") (pintype "input"))
      (node (ref "R8") (pin "1") (pinfunction "1_1") (pintype "input"))
    )
    (net (code "2") (name "+3.3V") (class "Default")
      (node (ref "C1") (pin "2") (pinfunction "2_2") (pintype "unspecified"))
      (node (ref "C10") (pin "2") (pinfunction "2_2") (pintype "unspecified"))
      (node (ref "C14") (pin "2") (pinfunction "2_2") (pintype "unspecified"))
      (node (ref "C18") (pin "2") (pinfunction "2_2") (pintype "unspecified"))
      (node (ref "C26") (pin "1") (pinfunction "1_1") (pintype "unspecified"))
      (node (ref "C29") (pin "1") (pinfunction "1_1") (pintype "unspecified"))
      (node (ref "C31") (pin "2") (pinfunction "2_2") (pintype "unspecified"))
      (node (ref "C33") (pin "2") (pinfunction "2_2") (pintype "unspecified"))
      (node (ref "FPC1") (pin "5") (pinfunction "5_5") (pintype "input"))
      (node (ref "R1") (pin "1") (pinfunction "1_1") (pintype "input"))
      (node (ref "R2") (pin "1") (pinfunction "1_1") (pintype "input"))
      (node (ref "R57") (pin "1") (pinfunction "1_1") (pintype "input"))
      (node (ref "R66") (pin "1") (pinfunction "1_1") (pintype "input"))
      (node (ref "R67") (pin "1") (pinfunction "1_1") (pintype "input"))
      (node (ref "U1") (pin "3") (pinfunction "VDD_3") (pintype "unspecified"))
      (node (ref "U12") (pin "8") (pinfunction "VCC_8") (pintype "input"))
      (node (ref "U2") (pin "1") (pinfunction "VDD_1") (pintype "unspecified"))
      (node (ref "U2") (pin "7") (pinfunction "VDDO_7") (pintype "unspecified"))
      (node (ref "U4") (pin "1") (pinfunction "VDD_1") (pintype "input"))
      (node (ref "U4") (pin "24") (pinfunction "VDD_24") (pintype "input"))
      (node (ref "U4") (pin "48") (pinfunction "VDD_48") (pintype "input"))
      (node (ref "U4") (pin "9") (pinfunction "VDDA_9") (pintype "input"))
      (node (ref "U7") (pin "2") (pinfunction "VOUT_2") (pintype "input"))
    )
    (net (code "3") (name "+4.5V") (class "Default")
      (node (ref "C17") (pin "2") (pinfunction "2_2") (pintype "unspecified"))
      (node (ref "C37") (pin "2") (pinfunction "2_2") (pintype "unspecified"))
      (node (ref "C38") (pin "2") (pinfunction "2_2") (pintype "unspecified"))
      (node (ref "C9") (pin "2") (pinfunction "2_2") (pintype "unspecified"))
      (node (ref "D1") (pin "1") (pinfunction "K_1") (pintype "unspecified"))
      (node (ref "R60") (pin "1") (pinfunction "1_1") (pintype "input"))
      (node (ref "R61") (pin "1") (pinfunction "1_1") (pintype "input"))
      (node (ref "U3") (pin "8") (pinfunction "VCC_8") (pintype "input"))
      (node (ref "U5") (pin "8") (pinfunction "VCC_8") (pintype "input"))
    )
    (net (code "4") (name "/BT+") (class "Default")
      (node (ref "BT1") (pin "2") (pinfunction "2_2") (pintype "input"))
      (node (ref "C28") (pin "2") (pinfunction "2_2") (pintype "unspecified"))
      (node (ref "R59") (pin "2") (pinfunction "2_2") (pintype "input"))
      (node (ref "SW3") (pin "3") (pinfunction "3_3") (pintype "unspecified"))
      (node (ref "U6") (pin "5") (pinfunction "BAT_5") (pintype "input"))
    )
    (net (code "5") (name "/BT-") (class "Default")
      (node (ref "BT1") (pin "1") (pinfunction "1_1") (pintype "input"))
      (node (ref "C32") (pin "1") (pinfunction "1_1") (pintype "unspecified"))
      (node (ref "U10") (pin "2") (pinfunction "S_2") (pintype "input"))
      (node (ref "U8") (pin "6") (pinfunction "GND_6") (pintype "input"))
    )
    (net (code "6") (name "/PA0_ADC0") (class "Default")
      (node (ref "R24") (pin "2") (pinfunction "2_2") (pintype "unspecified"))
      (node (ref "U12") (pin "1") (pinfunction "OUT_1") (pintype "output"))
      (node (ref "U4") (pin "10") (pinfunction "PA0_10") (pintype "input"))
    )
    (net (code "7") (name "/PA1_ADC1") (class "Default")
      (node (ref "R48") (pin "2") (pinfunction "2_2") (pintype "unspecified"))
      (node (ref "U12") (pin "7") (pinfunction "OUT2_7") (pintype "output"))
      (node (ref "U4") (pin "11") (pinfunction "PA1_11") (pintype "input"))
    )
    (net (code "8") (name "/PA13_SWDIO") (class "Default")
      (node (ref "H3") (pin "1") (pinfunction "1_1") (pintype "unspecified"))
      (node (ref "U4") (pin "34") (pinfunction "PA13_34") (pintype "input"))
    )
    (net (code "9") (name "/PA14_SWCLK") (class "Default")
      (node (ref "H1") (pin "1") (pinfunction "1_1") (pintype "unspecified"))
      (node (ref "U4") (pin "37") (pinfunction "PA14_37") (pintype "input"))
    )
    (net (code "10") (name "/PA15_SPI1_CS_LCD_A0") (class "Default")
      (node (ref "FPC1") (pin "8") (pinfunction "8_8") (pintype "input"))
      (node (ref "U4") (pin "38") (pinfunction "PA15_38") (pintype "input"))
    )
    (net (code "11") (name "/PB3_SPI1_SCK") (class "Default")
      (node (ref "FPC1") (pin "7") (pinfunction "7_7") (pintype "input"))
      (node (ref "U4") (pin "39") (pinfunction "PB3_39") (pintype "input"))
    )
    (net (code "12") (name "/PB4_LCD_RST") (class "Default")
      (node (ref "FPC1") (pin "9") (pinfunction "9_9") (pintype "input"))
      (node (ref "U4") (pin "40") (pinfunction "PB4_40") (pintype "input"))
    )
    (net (code "13") (name "/PB5_SPI1_MOSI") (class "Default")
      (node (ref "FPC1") (pin "6") (pinfunction "6_6") (pintype "input"))
      (node (ref "U4") (pin "41") (pinfunction "PB5_41") (pintype "input"))
    )
    (net (code "14") (name "/SI5351_CLK2_MCU_OSC_IN") (class "Default")
      (node (ref "U2") (pin "6") (pinfunction "CLK2_6") (pintype "unspecified"))
      (node (ref "U4") (pin "5") (pinfunction "PF0-OSC_IN_5") (pintype "input"))
    )
    (net (code "15") (name "/SI5351_SCL_PA4_SCL") (class "Default")
      (node (ref "R67") (pin "2") (pinfunction "2_2") (pintype "input"))
      (node (ref "U2") (pin "4") (pinfunction "SCL_4") (pintype "unspecified"))
      (node (ref "U4") (pin "13") (pinfunction "PA3_13") (pintype "input"))
    )
    (net (code "16") (name "/SI5351_SDA_PA5_SDA") (class "Default")
      (node (ref "R66") (pin "2") (pinfunction "2_2") (pintype "input"))
      (node (ref "U2") (pin "5") (pinfunction "SDA_5") (pintype "unspecified"))
      (node (ref "U4") (pin "14") (pinfunction "PA4_14") (pintype "input"))
    )
    (net (code "17") (name "GND") (class "Default")
      (node (ref "C1") (pin "1") (pinfunction "1_1") (pintype "unspecified"))
      (node (ref "C10") (pin "1") (pinfunction "1_1") (pintype "unspecified"))
      (node (ref "C11") (pin "1") (pinfunction "1_1") (pintype "input"))
      (node (ref "C13") (pin "1") (pinfunction "1_1") (pintype "input"))
      (node (ref "C14") (pin "1") (pinfunction "1_1") (pintype "unspecified"))
      (node (ref "C17") (pin "1") (pinfunction "1_1") (pintype "unspecified"))
      (node (ref "C18") (pin "1") (pinfunction "1_1") (pintype "unspecified"))
      (node (ref "C20") (pin "1") (pinfunction "1_1") (pintype "input"))
      (node (ref "C21") (pin "1") (pinfunction "1_1") (pintype "unspecified"))
      (node (ref "C25") (pin "1") (pinfunction "1_1") (pintype "input"))
      (node (ref "C26") (pin "2") (pinfunction "2_2") (pintype "unspecified"))
      (node (ref "C27") (pin "1") (pinfunction "1_1") (pintype "unspecified"))
      (node (ref "C28") (pin "1") (pinfunction "1_1") (pintype "unspecified"))
      (node (ref "C29") (pin "2") (pinfunction "2_2") (pintype "unspecified"))
      (node (ref "C3") (pin "1") (pinfunction "1_1") (pintype "unspecified"))
      (node (ref "C30") (pin "1") (pinfunction "1_1") (pintype "unspecified"))
      (node (ref "C31") (pin "1") (pinfunction "1_1") (pintype "unspecified"))
      (node (ref "C34") (pin "1") (pinfunction "1_1") (pintype "unspecified"))
      (node (ref "C36") (pin "2") (pinfunction "2_2") (pintype "unspecified"))
      (node (ref "C37") (pin "1") (pinfunction "1_1") (pintype "unspecified"))
      (node (ref "C38") (pin "1") (pinfunction "1_1") (pintype "unspecified"))
      (node (ref "C39") (pin "1") (pinfunction "1_1") (pintype "unspecified"))
      (node (ref "C40") (pin "1") (pinfunction "1_1") (pintype "unspecified"))
      (node (ref "C6") (pin "1") (pinfunction "1_1") (pintype "input"))
      (node (ref "C9") (pin "1") (pinfunction "1_1") (pintype "unspecified"))
      (node (ref "FPC1") (pin "10") (pinfunction "10_10") (pintype "input"))
      (node (ref "FPC1") (pin "11") (pinfunction "11_11") (pintype "input"))
      (node (ref "FPC1") (pin "12") (pinfunction "12_12") (pintype "input"))
      (node (ref "FPC1") (pin "4") (pinfunction "4_4") (pintype "input"))
      (node (ref "H2") (pin "1") (pinfunction "1_1") (pintype "unspecified"))
      (node (ref "R12") (pin "2") (pinfunction "2_2") (pintype "input"))
      (node (ref "R13") (pin "1") (pinfunction "1_1") (pintype "input"))
      (node (ref "R14") (pin "1") (pinfunction "1_1") (pintype "input"))
      (node (ref "R15") (pin "1") (pinfunction "1_1") (pintype "input"))
      (node (ref "R29") (pin "1") (pinfunction "1_1") (pintype "input"))
      (node (ref "R30") (pin "1") (pinfunction "1_1") (pintype "input"))
      (node (ref "R31") (pin "1") (pinfunction "1_1") (pintype "input"))
      (node (ref "R33") (pin "1") (pinfunction "1_1") (pintype "input"))
      (node (ref "R36") (pin "1") (pinfunction "1_1") (pintype "input"))
      (node (ref "R43") (pin "1") (pinfunction "1_1") (pintype "input"))
      (node (ref "R52") (pin "2") (pinfunction "2_2") (pintype "input"))
      (node (ref "R53") (pin "2") (pinfunction "2_2") (pintype "input"))
      (node (ref "R55") (pin "2") (pinfunction "2_2") (pintype "input"))
      (node (ref "R56") (pin "2") (pinfunction "2_2") (pintype "input"))
      (node (ref "R58") (pin "2") (pinfunction "2_2") (pintype "input"))
      (node (ref "R62") (pin "1") (pinfunction "1_1") (pintype "input"))
      (node (ref "R64") (pin "2") (pinfunction "2_2") (pintype "input"))
      (node (ref "RF1") (pin "1") (pinfunction "1_1") (pintype "unspecified"))
      (node (ref "RF1") (pin "2") (pinfunction "2_2") (pintype "unspecified"))
      (node (ref "RF1") (pin "3") (pinfunction "3_3") (pintype "unspecified"))
      (node (ref "RF1") (pin "4") (pinfunction "4_4") (pintype "unspecified"))
      (node (ref "SCREW1") (pin "1") (pinfunction "1_1") (pintype "input"))
      (node (ref "SCREW2") (pin "1") (pinfunction "1_1") (pintype "input"))
      (node (ref "SCREW3") (pin "1") (pinfunction "1_1") (pintype "input"))
      (node (ref "SCREW4") (pin "1") (pinfunction "1_1") (pintype "input"))
      (node (ref "SCREW5") (pin "1") (pinfunction "1_1") (pintype "input"))
      (node (ref "SW1") (pin "1") (pinfunction "1_1") (pintype "input"))
      (node (ref "SW1") (pin "2") (pinfunction "2_2") (pintype "input"))
      (node (ref "SW2") (pin "1") (pinfunction "1_1") (pintype "input"))
      (node (ref "SW2") (pin "2") (pinfunction "2_2") (pintype "input"))
      (node (ref "U1") (pin "4") (pinfunction "VSS_4") (pintype "unspecified"))
      (node (ref "U1") (pin "5") (pinfunction "EP_5") (pintype "unspecified"))
      (node (ref "U11") (pin "2") (pinfunction "S_2") (pintype "input"))
      (node (ref "U12") (pin "4") (pinfunction "GND_4") (pintype "input"))
      (node (ref "U2") (pin "8") (pinfunction "GND_8") (pintype "unspecified"))
      (node (ref "U3") (pin "3") (pinfunction "GND_3") (pintype "input"))
      (node (ref "U4") (pin "23") (pinfunction "VSS_23") (pintype "input"))
      (node (ref "U4") (pin "47") (pinfunction "VSS_47") (pintype "input"))
      (node (ref "U4") (pin "8") (pinfunction "VSSA_8") (pintype "input"))
      (node (ref "U5") (pin "3") (pinfunction "GND_3") (pintype "input"))
      (node (ref "U6") (pin "1") (pinfunction "TEMP_1") (pintype "input"))
      (node (ref "U6") (pin "3") (pinfunction "GND_3") (pintype "input"))
      (node (ref "U7") (pin "1") (pinfunction "VSS_1") (pintype "input"))
      (node (ref "U9") (pin "2") (pinfunction "GND_2") (pintype "input"))
      (node (ref "USB1") (pin "1") (pinfunction "GND_1") (pintype "input"))
      (node (ref "USB1") (pin "12") (pinfunction "GND_12") (pintype "input"))
      (node (ref "USB1") (pin "13") (pinfunction "SHELL_13") (pintype "input"))
      (node (ref "USB1") (pin "14") (pinfunction "SHELL_14") (pintype "input"))
      (node (ref "X1") (pin "2") (pinfunction "GND_2") (pintype "unspecified"))
      (node (ref "X1") (pin "4") (pinfunction "GND_4") (pintype "unspecified"))
    )
    (net (code "18") (name "Net-(C2-Pad1)") (class "Default")
      (node (ref "C2") (pin "1") (pinfunction "1_1") (pintype "input"))
      (node (ref "R19") (pin "2") (pinfunction "2_2") (pintype "input"))
      (node (ref "R37") (pin "2") (pinfunction "2_2") (pintype "input"))
    )
    (net (code "19") (name "Net-(C3-Pad2)") (class "Default")
      (node (ref "C3") (pin "2") (pinfunction "2_2") (pintype "unspecified"))
      (node (ref "R4") (pin "2") (pinfunction "2_2") (pintype "unspecified"))
    )
    (net (code "20") (name "Net-(C4-Pad1)") (class "Default")
      (node (ref "C4") (pin "1") (pinfunction "1_1") (pintype "input"))
      (node (ref "R10") (pin "2") (pinfunction "2_2") (pintype "input"))
      (node (ref "R16") (pin "2") (pinfunction "2_2") (pintype "input"))
    )
    (net (code "21") (name "Net-(C5-Pad1)") (class "Default")
      (node (ref "C5") (pin "1") (pinfunction "1_1") (pintype "unspecified"))
      (node (ref "C6") (pin "2") (pinfunction "2_2") (pintype "input"))
      (node (ref "R5") (pin "2") (pinfunction "2_2") (pintype "input"))
    )
    (net (code "22") (name "Net-(C5-Pad2)") (class "Default")
      (node (ref "C5") (pin "2") (pinfunction "2_2") (pintype "unspecified"))
      (node (ref "R11") (pin "1") (pinfunction "1_1") (pintype "unspecified"))
      (node (ref "R3") (pin "1") (pinfunction "1_1") (pintype "unspecified"))
      (node (ref "R8") (pin "2") (pinfunction "2_2") (pintype "input"))
      (node (ref "R9") (pin "1") (pinfunction "1_1") (pintype "unspecified"))
    )
    (net (code "23") (name "Net-(C8-Pad1)") (class "Default")
      (node (ref "C8") (pin "1") (pinfunction "1_1") (pintype "input"))
      (node (ref "R10") (pin "1") (pinfunction "1_1") (pintype "input"))
      (node (ref "R13") (pin "2") (pinfunction "2_2") (pintype "input"))
      (node (ref "R14") (pin "2") (pinfunction "2_2") (pintype "input"))
      (node (ref "R15") (pin "2") (pinfunction "2_2") (pintype "input"))
    )
    (net (code "24") (name "Net-(C12-Pad1)") (class "Default")
      (node (ref "C12") (pin "1") (pinfunction "1_1") (pintype "unspecified"))
      (node (ref "C13") (pin "2") (pinfunction "2_2") (pintype "input"))
      (node (ref "R20") (pin "2") (pinfunction "2_2") (pintype "input"))
    )
    (net (code "25") (name "Net-(C12-Pad2)") (class "Default")
      (node (ref "C12") (pin "2") (pinfunction "2_2") (pintype "unspecified"))
      (node (ref "R17") (pin "1") (pinfunction "1_1") (pintype "unspecified"))
      (node (ref "R21") (pin "1") (pinfunction "1_1") (pintype "unspecified"))
      (node (ref "R22") (pin "2") (pinfunction "2_2") (pintype "input"))
      (node (ref "R23") (pin "1") (pinfunction "1_1") (pintype "unspecified"))
    )
    (net (code "26") (name "Net-(C15-Pad2)") (class "Default")
      (node (ref "C15") (pin "2") (pinfunction "2_2") (pintype "input"))
      (node (ref "R19") (pin "1") (pinfunction "1_1") (pintype "input"))
      (node (ref "R29") (pin "2") (pinfunction "2_2") (pintype "input"))
    )
    (net (code "27") (name "Net-(C16-Pad1)") (class "Default")
      (node (ref "C16") (pin "1") (pinfunction "1_1") (pintype "input"))
      (node (ref "R32") (pin "1") (pinfunction "1_1") (pintype "input"))
      (node (ref "R33") (pin "2") (pinfunction "2_2") (pintype "input"))
    )
    (net (code "28") (name "Net-(C19-Pad1)") (class "Default")
      (node (ref "C19") (pin "1") (pinfunction "1_1") (pintype "unspecified"))
      (node (ref "C20") (pin "2") (pinfunction "2_2") (pintype "input"))
      (node (ref "R35") (pin "2") (pinfunction "2_2") (pintype "input"))
    )
    (net (code "29") (name "Net-(C19-Pad2)") (class "Default")
      (node (ref "C19") (pin "2") (pinfunction "2_2") (pintype "unspecified"))
      (node (ref "R34") (pin "1") (pinfunction "1_1") (pintype "unspecified"))
      (node (ref "R38") (pin "2") (pinfunction "2_2") (pintype "input"))
      (node (ref "R39") (pin "1") (pinfunction "1_1") (pintype "unspecified"))
      (node (ref "R42") (pin "1") (pinfunction "1_1") (pintype "unspecified"))
    )
    (net (code "30") (name "Net-(C21-Pad2)") (class "Default")
      (node (ref "C21") (pin "2") (pinfunction "2_2") (pintype "unspecified"))
      (node (ref "R40") (pin "2") (pinfunction "2_2") (pintype "unspecified"))
    )
    (net (code "31") (name "Net-(C22-Pad1)") (class "Default")
      (node (ref "C22") (pin "1") (pinfunction "1_1") (pintype "input"))
      (node (ref "R36") (pin "2") (pinfunction "2_2") (pintype "input"))
      (node (ref "R41") (pin "1") (pinfunction "1_1") (pintype "input"))
    )
    (net (code "32") (name "Net-(C23-Pad2)") (class "Default")
      (node (ref "C23") (pin "2") (pinfunction "2_2") (pintype "input"))
      (node (ref "R37") (pin "1") (pinfunction "1_1") (pintype "input"))
      (node (ref "R43") (pin "2") (pinfunction "2_2") (pintype "input"))
    )
    (net (code "33") (name "Net-(C24-Pad1)") (class "Default")
      (node (ref "C24") (pin "1") (pinfunction "1_1") (pintype "unspecified"))
      (node (ref "C25") (pin "2") (pinfunction "2_2") (pintype "input"))
      (node (ref "R44") (pin "2") (pinfunction "2_2") (pintype "input"))
    )
    (net (code "34") (name "Net-(C24-Pad2)") (class "Default")
      (node (ref "C24") (pin "2") (pinfunction "2_2") (pintype "unspecified"))
      (node (ref "R45") (pin "1") (pinfunction "1_1") (pintype "unspecified"))
      (node (ref "R46") (pin "2") (pinfunction "2_2") (pintype "input"))
      (node (ref "R47") (pin "1") (pinfunction "1_1") (pintype "unspecified"))
      (node (ref "R49") (pin "1") (pinfunction "1_1") (pintype "unspecified"))
    )
    (net (code "35") (name "Net-(C35-Pad1)") (class "Default")
      (node (ref "C35") (pin "1") (pinfunction "1_1") (pintype "unspecified"))
      (node (ref "FPC1") (pin "3") (pinfunction "3_3") (pintype "input"))
    )
    (net (code "36") (name "Net-(C35-Pad2)") (class "Default")
      (node (ref "C35") (pin "2") (pinfunction "2_2") (pintype "unspecified"))
      (node (ref "FPC1") (pin "2") (pinfunction "2_2") (pintype "input"))
    )
    (net (code "37") (name "Net-(C36-Pad1)") (class "Default")
      (node (ref "C36") (pin "1") (pinfunction "1_1") (pintype "unspecified"))
      (node (ref "FPC1") (pin "1") (pinfunction "1_1") (pintype "input"))
    )
    (net (code "38") (name "Net-(D1-A)") (class "Default")
      (node (ref "D1") (pin "2") (pinfunction "A_2") (pintype "unspecified"))
      (node (ref "L1") (pin "1") (pinfunction "1_1") (pintype "input"))
      (node (ref "U9") (pin "1") (pinfunction "SW_1") (pintype "input"))
    )
    (net (code "39") (name "Net-(LED1-A)") (class "Default")
      (node (ref "C27") (pin "2") (pinfunction "2_2") (pintype "unspecified"))
      (node (ref "LED1") (pin "1") (pinfunction "A_1") (pintype "input"))
      (node (ref "LED2") (pin "1") (pinfunction "A_1") (pintype "input"))
      (node (ref "U6") (pin "4") (pinfunction "Vcc_4") (pintype "input"))
      (node (ref "U6") (pin "8") (pinfunction "CE_8") (pintype "input"))
      (node (ref "USB1") (pin "11") (pinfunction "VBUS_11") (pintype "input"))
      (node (ref "USB1") (pin "2") (pinfunction "VBUS_2") (pintype "input"))
    )
    (net (code "40") (name "Net-(LED1-K)") (class "Default")
      (node (ref "LED1") (pin "2") (pinfunction "K_2") (pintype "input"))
      (node (ref "R50") (pin "2") (pinfunction "2_2") (pintype "input"))
    )
    (net (code "41") (name "Net-(LED2-K)") (class "Default")
      (node (ref "LED2") (pin "2") (pinfunction "K_2") (pintype "input"))
      (node (ref "R51") (pin "2") (pinfunction "2_2") (pintype "input"))
    )
    (net (code "42") (name "Net-(R6-Pad1)") (class "Default")
      (node (ref "R6") (pin "1") (pinfunction "1_1") (pintype "input"))
      (node (ref "SW1") (pin "3") (pinfunction "3_3") (pintype "input"))
      (node (ref "SW1") (pin "4") (pinfunction "4_4") (pintype "input"))
    )
    (net (code "43") (name "Net-(R7-Pad1)") (class "Default")
      (node (ref "R7") (pin "1") (pinfunction "1_1") (pintype "input"))
      (node (ref "SW2") (pin "3") (pinfunction "3_3") (pintype "input"))
      (node (ref "SW2") (pin "4") (pinfunction "4_4") (pintype "input"))
    )
    (net (code "44") (name "Net-(R16-Pad1)") (class "Default")
      (node (ref "R16") (pin "1") (pinfunction "1_1") (pintype "input"))
      (node (ref "R18") (pin "2") (pinfunction "2_2") (pintype "input"))
    )
    (net (code "45") (name "Net-(R18-Pad1)") (class "Default")
      (node (ref "R18") (pin "1") (pinfunction "1_1") (pintype "input"))
      (node (ref "R25") (pin "2") (pinfunction "2_2") (pintype "input"))
      (node (ref "R26") (pin "2") (pinfunction "2_2") (pintype "input"))
      (node (ref "R27") (pin "2") (pinfunction "2_2") (pintype "input"))
      (node (ref "R28") (pin "2") (pinfunction "2_2") (pintype "input"))
    )
    (net (code "46") (name "Net-(R25-Pad1)") (class "Default")
      (node (ref "R25") (pin "1") (pinfunction "1_1") (pintype "input"))
      (node (ref "R26") (pin "1") (pinfunction "1_1") (pintype "input"))
      (node (ref "R41") (pin "2") (pinfunction "2_2") (pintype "input"))
      (node (ref "RF1") (pin "5") (pinfunction "5_5") (pintype "unspecified"))
    )
    (net (code "47") (name "Net-(R27-Pad1)") (class "Default")
      (node (ref "R27") (pin "1") (pinfunction "1_1") (pintype "input"))
      (node (ref "R28") (pin "1") (pinfunction "1_1") (pintype "input"))
      (node (ref "R30") (pin "2") (pinfunction "2_2") (pintype "input"))
      (node (ref "R31") (pin "2") (pinfunction "2_2") (pintype "input"))
      (node (ref "R32") (pin "2") (pinfunction "2_2") (pintype "input"))
    )
    (net (code "48") (name "Net-(R53-Pad1)") (class "Default")
      (node (ref "R53") (pin "1") (pinfunction "1_1") (pintype "input"))
      (node (ref "R54") (pin "2") (pinfunction "2_2") (pintype "input"))
      (node (ref "R56") (pin "1") (pinfunction "1_1") (pintype "input"))
    )
    (net (code "49") (name "Net-(R61-Pad2)") (class "Default")
      (node (ref "R61") (pin "2") (pinfunction "2_2") (pintype "input"))
      (node (ref "R63") (pin "2") (pinfunction "2_2") (pintype "input"))
    )
    (net (code "50") (name "Net-(U1-SCL)") (class "Default")
      (node (ref "R1") (pin "2") (pinfunction "2_2") (pintype "input"))
      (node (ref "U1") (pin "2") (pinfunction "SCL_2") (pintype "unspecified"))
      (node (ref "U4") (pin "45") (pinfunction "PB8_45") (pintype "input"))
    )
    (net (code "51") (name "Net-(U1-SDA)") (class "Default")
      (node (ref "R2") (pin "2") (pinfunction "2_2") (pintype "input"))
      (node (ref "U1") (pin "1") (pinfunction "SDA_1") (pintype "unspecified"))
      (node (ref "U4") (pin "46") (pinfunction "PB9_46") (pintype "input"))
    )
    (net (code "52") (name "Net-(U2-CLK0)") (class "Default")
      (node (ref "C2") (pin "2") (pinfunction "2_2") (pintype "input"))
      (node (ref "U2") (pin "10") (pinfunction "CLK0_10") (pintype "unspecified"))
    )
    (net (code "53") (name "Net-(U2-CLK1)") (class "Default")
      (node (ref "C4") (pin "2") (pinfunction "2_2") (pintype "input"))
      (node (ref "U2") (pin "9") (pinfunction "CLK1_9") (pintype "unspecified"))
    )
    (net (code "54") (name "Net-(U2-XA)") (class "Default")
      (node (ref "U2") (pin "2") (pinfunction "XA_2") (pintype "unspecified"))
      (node (ref "X1") (pin "3") (pinfunction "OSC2_3") (pintype "unspecified"))
    )
    (net (code "55") (name "Net-(U2-XB)") (class "Default")
      (node (ref "U2") (pin "3") (pinfunction "XB_3") (pintype "unspecified"))
      (node (ref "X1") (pin "1") (pinfunction "OSC1_1") (pintype "unspecified"))
    )
    (net (code "56") (name "Net-(U3-IN_A)") (class "Default")
      (node (ref "C8") (pin "2") (pinfunction "2_2") (pintype "input"))
      (node (ref "U3") (pin "1") (pinfunction "IN_A_1") (pintype "input"))
    )
    (net (code "57") (name "Net-(U3-IN_B)") (class "Default")
      (node (ref "C11") (pin "2") (pinfunction "2_2") (pintype "input"))
      (node (ref "U3") (pin "2") (pinfunction "IN_B_2") (pintype "input"))
    )
    (net (code "58") (name "Net-(U3-OSC_B)") (class "Default")
      (node (ref "C15") (pin "1") (pinfunction "1_1") (pintype "input"))
      (node (ref "U3") (pin "6") (pinfunction "OSC_B_6") (pintype "input"))
    )
    (net (code "59") (name "Net-(U3-OUT_A)") (class "Default")
      (node (ref "R20") (pin "1") (pinfunction "1_1") (pintype "input"))
      (node (ref "U3") (pin "4") (pinfunction "OUT_A_4") (pintype "input"))
    )
    (net (code "60") (name "Net-(U3-OUT_B)") (class "Default")
      (node (ref "R5") (pin "1") (pinfunction "1_1") (pintype "input"))
      (node (ref "U3") (pin "5") (pinfunction "OUT_B_5") (pintype "input"))
    )
    (net (code "61") (name "Net-(U4-BOOT0)") (class "Default")
      (node (ref "R12") (pin "1") (pinfunction "1_1") (pintype "input"))
      (node (ref "U4") (pin "44") (pinfunction "BOOT0_44") (pintype "input"))
    )
    (net (code "62") (name "Net-(U4-PB6)") (class "Default")
      (node (ref "R7") (pin "2") (pinfunction "2_2") (pintype "input"))
      (node (ref "U4") (pin "42") (pinfunction "PB6_42") (pintype "input"))
    )
    (net (code "63") (name "Net-(U4-PB7)") (class "Default")
      (node (ref "R6") (pin "2") (pinfunction "2_2") (pintype "input"))
      (node (ref "U4") (pin "43") (pinfunction "PB7_43") (pintype "input"))
    )
    (net (code "64") (name "Net-(U5-IN_A)") (class "Default")
      (node (ref "C16") (pin "2") (pinfunction "2_2") (pintype "input"))
      (node (ref "U5") (pin "1") (pinfunction "IN_A_1") (pintype "input"))
    )
    (net (code "65") (name "Net-(U5-IN_B)") (class "Default")
      (node (ref "C22") (pin "2") (pinfunction "2_2") (pintype "input"))
      (node (ref "U5") (pin "2") (pinfunction "IN_B_2") (pintype "input"))
    )
    (net (code "66") (name "Net-(U5-OSC_B)") (class "Default")
      (node (ref "C23") (pin "1") (pinfunction "1_1") (pintype "input"))
      (node (ref "U5") (pin "6") (pinfunction "OSC_B_6") (pintype "input"))
    )
    (net (code "67") (name "Net-(U5-OUT_A)") (class "Default")
      (node (ref "R44") (pin "1") (pinfunction "1_1") (pintype "input"))
      (node (ref "U5") (pin "4") (pinfunction "OUT_A_4") (pintype "input"))
    )
    (net (code "68") (name "Net-(U5-OUT_B)") (class "Default")
      (node (ref "R35") (pin "1") (pinfunction "1_1") (pintype "input"))
      (node (ref "U5") (pin "5") (pinfunction "OUT_B_5") (pintype "input"))
    )
    (net (code "69") (name "Net-(U6-CHRG#)") (class "Default")
      (node (ref "R50") (pin "1") (pinfunction "1_1") (pintype "input"))
      (node (ref "U6") (pin "7") (pinfunction "CHRG#_7") (pintype "input"))
    )
    (net (code "70") (name "Net-(U6-PROG)") (class "Default")
      (node (ref "R54") (pin "1") (pinfunction "1_1") (pintype "input"))
      (node (ref "U6") (pin "2") (pinfunction "PROG_2") (pintype "input"))
    )
    (net (code "71") (name "Net-(U6-STDBY#)") (class "Default")
      (node (ref "R51") (pin "1") (pinfunction "1_1") (pintype "input"))
      (node (ref "U6") (pin "6") (pinfunction "STDBY#_6") (pintype "input"))
    )
    (net (code "72") (name "Net-(U8-CS)") (class "Default")
      (node (ref "R62") (pin "2") (pinfunction "2_2") (pintype "input"))
      (node (ref "U8") (pin "2") (pinfunction "CS_2") (pintype "input"))
    )
    (net (code "73") (name "Net-(U8-VCC)") (class "Default")
      (node (ref "C32") (pin "2") (pinfunction "2_2") (pintype "unspecified"))
      (node (ref "R59") (pin "1") (pinfunction "1_1") (pintype "input"))
      (node (ref "U8") (pin "5") (pinfunction "VCC_5") (pintype "input"))
    )
    (net (code "74") (name "Net-(U9-EN)") (class "Default")
      (node (ref "R65") (pin "2") (pinfunction "2_2") (pintype "input"))
      (node (ref "U9") (pin "4") (pinfunction "EN_4") (pintype "input"))
    )
    (net (code "75") (name "Net-(U9-FB)") (class "Default")
      (node (ref "R60") (pin "2") (pinfunction "2_2") (pintype "input"))
      (node (ref "R63") (pin "1") (pinfunction "1_1") (pintype "input"))
      (node (ref "R64") (pin "1") (pinfunction "1_1") (pintype "input"))
      (node (ref "U9") (pin "3") (pinfunction "FB_3") (pintype "input"))
    )
    (net (code "76") (name "Net-(U10-D)") (class "Default")
      (node (ref "U10") (pin "3") (pinfunction "D_3") (pintype "input"))
      (node (ref "U11") (pin "3") (pinfunction "D_3") (pintype "input"))
    )
    (net (code "77") (name "Net-(U10-G)") (class "Default")
      (node (ref "U10") (pin "1") (pinfunction "G_1") (pintype "input"))
      (node (ref "U8") (pin "1") (pinfunction "OD_1") (pintype "input"))
    )
    (net (code "78") (name "Net-(U11-G)") (class "Default")
      (node (ref "U11") (pin "1") (pinfunction "G_1") (pintype "input"))
      (node (ref "U8") (pin "3") (pinfunction "OC_3") (pintype "input"))
    )
    (net (code "79") (name "Net-(U12A-IN1+)") (class "Default")
      (node (ref "R11") (pin "2") (pinfunction "2_2") (pintype "unspecified"))
      (node (ref "R3") (pin "2") (pinfunction "2_2") (pintype "unspecified"))
      (node (ref "R4") (pin "1") (pinfunction "1_1") (pintype "unspecified"))
      (node (ref "R9") (pin "2") (pinfunction "2_2") (pintype "unspecified"))
      (node (ref "U12") (pin "3") (pinfunction "IN1+_3") (pintype "input"))
    )
    (net (code "80") (name "Net-(U12A-IN1-)") (class "Default")
      (node (ref "R17") (pin "2") (pinfunction "2_2") (pintype "unspecified"))
      (node (ref "R21") (pin "2") (pinfunction "2_2") (pintype "unspecified"))
      (node (ref "R23") (pin "2") (pinfunction "2_2") (pintype "unspecified"))
      (node (ref "R24") (pin "1") (pinfunction "1_1") (pintype "unspecified"))
      (node (ref "U12") (pin "2") (pinfunction "IN1-_2") (pintype "input"))
    )
    (net (code "81") (name "Net-(U12B-IN2+)") (class "Default")
      (node (ref "R34") (pin "2") (pinfunction "2_2") (pintype "unspecified"))
      (node (ref "R39") (pin "2") (pinfunction "2_2") (pintype "unspecified"))
      (node (ref "R40") (pin "1") (pinfunction "1_1") (pintype "unspecified"))
      (node (ref "R42") (pin "2") (pinfunction "2_2") (pintype "unspecified"))
      (node (ref "U12") (pin "5") (pinfunction "IN2+_5") (pintype "input"))
    )
    (net (code "82") (name "Net-(U12B-IN2-)") (class "Default")
      (node (ref "R45") (pin "2") (pinfunction "2_2") (pintype "unspecified"))
      (node (ref "R47") (pin "2") (pinfunction "2_2") (pintype "unspecified"))
      (node (ref "R48") (pin "1") (pinfunction "1_1") (pintype "unspecified"))
      (node (ref "R49") (pin "2") (pinfunction "2_2") (pintype "unspecified"))
      (node (ref "U12") (pin "6") (pinfunction "IN2-_6") (pintype "input"))
    )
    (net (code "83") (name "Net-(USB1-CC1)") (class "Default")
      (node (ref "R55") (pin "1") (pinfunction "1_1") (pintype "input"))
      (node (ref "USB1") (pin "4") (pinfunction "CC1_4") (pintype "input"))
    )
    (net (code "84") (name "Net-(USB1-CC2)") (class "Default")
      (node (ref "R52") (pin "1") (pinfunction "1_1") (pintype "input"))
      (node (ref "USB1") (pin "10") (pinfunction "CC2_10") (pintype "input"))
    )
    (net (code "85") (name "VCC") (class "Default")
      (node (ref "C30") (pin "2") (pinfunction "2_2") (pintype "unspecified"))
      (node (ref "C39") (pin "2") (pinfunction "2_2") (pintype "unspecified"))
      (node (ref "C40") (pin "2") (pinfunction "2_2") (pintype "unspecified"))
      (node (ref "L1") (pin "2") (pinfunction "2_2") (pintype "input"))
      (node (ref "R65") (pin "1") (pinfunction "1_1") (pintype "input"))
      (node (ref "SW3") (pin "1") (pinfunction "1_1") (pintype "unspecified"))
      (node (ref "SW3") (pin "2") (pinfunction "2_2") (pintype "unspecified"))
      (node (ref "U7") (pin "3") (pinfunction "VIN_3") (pintype "input"))
      (node (ref "U9") (pin "5") (pinfunction "VIN_5") (pintype "input"))
    )
    (net (code "86") (name "unconnected-(MARK1-Pad1)") (class "Default")
      (node (ref "MARK1") (pin "1") (pinfunction "1_1") (pintype "input"))
    )
    (net (code "87") (name "unconnected-(MARK2-Pad1)") (class "Default")
      (node (ref "MARK2") (pin "1") (pinfunction "1_1") (pintype "input"))
    )
    (net (code "88") (name "unconnected-(U3-OSC_E-Pad7)") (class "Default")
      (node (ref "U3") (pin "7") (pinfunction "OSC_E_7") (pintype "input"))
    )
    (net (code "89") (name "unconnected-(U4-NRST-Pad7)") (class "Default")
      (node (ref "U4") (pin "7") (pinfunction "NRST_7") (pintype "input"))
    )
    (net (code "90") (name "unconnected-(U4-PA2-Pad12)") (class "Default")
      (node (ref "U4") (pin "12") (pinfunction "PA2_12") (pintype "input"))
    )
    (net (code "91") (name "unconnected-(U4-PA5-Pad15)") (class "Default")
      (node (ref "U4") (pin "15") (pinfunction "PA5_15") (pintype "input"))
    )
    (net (code "92") (name "unconnected-(U4-PA6-Pad16)") (class "Default")
      (node (ref "U4") (pin "16") (pinfunction "PA6_16") (pintype "input"))
    )
    (net (code "93") (name "unconnected-(U4-PA7-Pad17)") (class "Default")
      (node (ref "U4") (pin "17") (pinfunction "PA7_17") (pintype "input"))
    )
    (net (code "94") (name "unconnected-(U4-PA8-Pad29)") (class "Default")
      (node (ref "U4") (pin "29") (pinfunction "PA8_29") (pintype "input"))
    )
    (net (code "95") (name "unconnected-(U4-PA9-Pad30)") (class "Default")
      (node (ref "U4") (pin "30") (pinfunction "PA9_30") (pintype "input"))
    )
    (net (code "96") (name "unconnected-(U4-PA10-Pad31)") (class "Default")
      (node (ref "U4") (pin "31") (pinfunction "PA10_31") (pintype "input"))
    )
    (net (code "97") (name "unconnected-(U4-PA11-Pad32)") (class "Default")
      (node (ref "U4") (pin "32") (pinfunction "PA11_32") (pintype "input"))
    )
    (net (code "98") (name "unconnected-(U4-PA12-Pad33)") (class "Default")
      (node (ref "U4") (pin "33") (pinfunction "PA12_33") (pintype "input"))
    )
    (net (code "99") (name "unconnected-(U4-PB0-Pad18)") (class "Default")
      (node (ref "U4") (pin "18") (pinfunction "PB0_18") (pintype "input"))
    )
    (net (code "100") (name "unconnected-(U4-PB1-Pad19)") (class "Default")
      (node (ref "U4") (pin "19") (pinfunction "PB1_19") (pintype "input"))
    )
    (net (code "101") (name "unconnected-(U4-PB2-Pad20)") (class "Default")
      (node (ref "U4") (pin "20") (pinfunction "PB2_20") (pintype "input"))
    )
    (net (code "102") (name "unconnected-(U4-PB10-Pad21)") (class "Default")
      (node (ref "U4") (pin "21") (pinfunction "PB10_21") (pintype "input"))
    )
    (net (code "103") (name "unconnected-(U4-PB11-Pad22)") (class "Default")
      (node (ref "U4") (pin "22") (pinfunction "PB11_22") (pintype "input"))
    )
    (net (code "104") (name "unconnected-(U4-PB12-Pad25)") (class "Default")
      (node (ref "U4") (pin "25") (pinfunction "PB12_25") (pintype "input"))
    )
    (net (code "105") (name "unconnected-(U4-PB13-Pad26)") (class "Default")
      (node (ref "U4") (pin "26") (pinfunction "PB13_26") (pintype "input"))
    )
    (net (code "106") (name "unconnected-(U4-PB14-Pad27)") (class "Default")
      (node (ref "U4") (pin "27") (pinfunction "PB14_27") (pintype "input"))
    )
    (net (code "107") (name "unconnected-(U4-PB15-Pad28)") (class "Default")
      (node (ref "U4") (pin "28") (pinfunction "PB15_28") (pintype "input"))
    )
    (net (code "108") (name "unconnected-(U4-PC13-Pad2)") (class "Default")
      (node (ref "U4") (pin "2") (pinfunction "PC13_2") (pintype "input"))
    )
    (net (code "109") (name "unconnected-(U4-PC14-OSC32_IN-Pad3)") (class "Default")
      (node (ref "U4") (pin "3") (pinfunction "PC14-OSC32_IN_3") (pintype "input"))
    )
    (net (code "110") (name "unconnected-(U4-PC15-OSC32_OUT-Pad4)") (class "Default")
      (node (ref "U4") (pin "4") (pinfunction "PC15-OSC32_OUT_4") (pintype "input"))
    )
    (net (code "111") (name "unconnected-(U4-PF1-OSC_OUT-Pad6)") (class "Default")
      (node (ref "U4") (pin "6") (pinfunction "PF1-OSC_OUT_6") (pintype "input"))
    )
    (net (code "112") (name "unconnected-(U4-PF6-Pad35)") (class "Default")
      (node (ref "U4") (pin "35") (pinfunction "PF6_35") (pintype "input"))
    )
    (net (code "113") (name "unconnected-(U4-PF7-Pad36)") (class "Default")
      (node (ref "U4") (pin "36") (pinfunction "PF7_36") (pintype "input"))
    )
    (net (code "114") (name "unconnected-(U5-OSC_E-Pad7)") (class "Default")
      (node (ref "U5") (pin "7") (pinfunction "OSC_E_7") (pintype "input"))
    )
    (net (code "115") (name "unconnected-(U8-TD-Pad4)") (class "Default")
      (node (ref "U8") (pin "4") (pinfunction "TD_4") (pintype "input"))
    )
    (net (code "116") (name "unconnected-(U9-NC-Pad6)") (class "Default")
      (node (ref "U9") (pin "6") (pinfunction "NC_6") (pintype "input"))
    )
    (net (code "117") (name "unconnected-(USB1-DN1-Pad7)") (class "Default")
      (node (ref "USB1") (pin "7") (pinfunction "DN1_7") (pintype "input"))
    )
    (net (code "118") (name "unconnected-(USB1-DN2-Pad5)") (class "Default")
      (node (ref "USB1") (pin "5") (pinfunction "DN2_5") (pintype "input"))
    )
    (net (code "119") (name "unconnected-(USB1-DP1-Pad6)") (class "Default")
      (node (ref "USB1") (pin "6") (pinfunction "DP1_6") (pintype "input"))
    )
    (net (code "120") (name "unconnected-(USB1-DP2-Pad8)") (class "Default")
      (node (ref "USB1") (pin "8") (pinfunction "DP2_8") (pintype "input"))
    )
    (net (code "121") (name "unconnected-(USB1-SBU1-Pad9)") (class "Default")
      (node (ref "USB1") (pin "9") (pinfunction "SBU1_9") (pintype "input"))
    )
    (net (code "122") (name "unconnected-(USB1-SBU2-Pad3)") (class "Default")
      (node (ref "USB1") (pin "3") (pinfunction "SBU2_3") (pintype "input"))
    )
  )
)
